# 4.net
KiCad netlist of a schematic drawn in Altium Designer
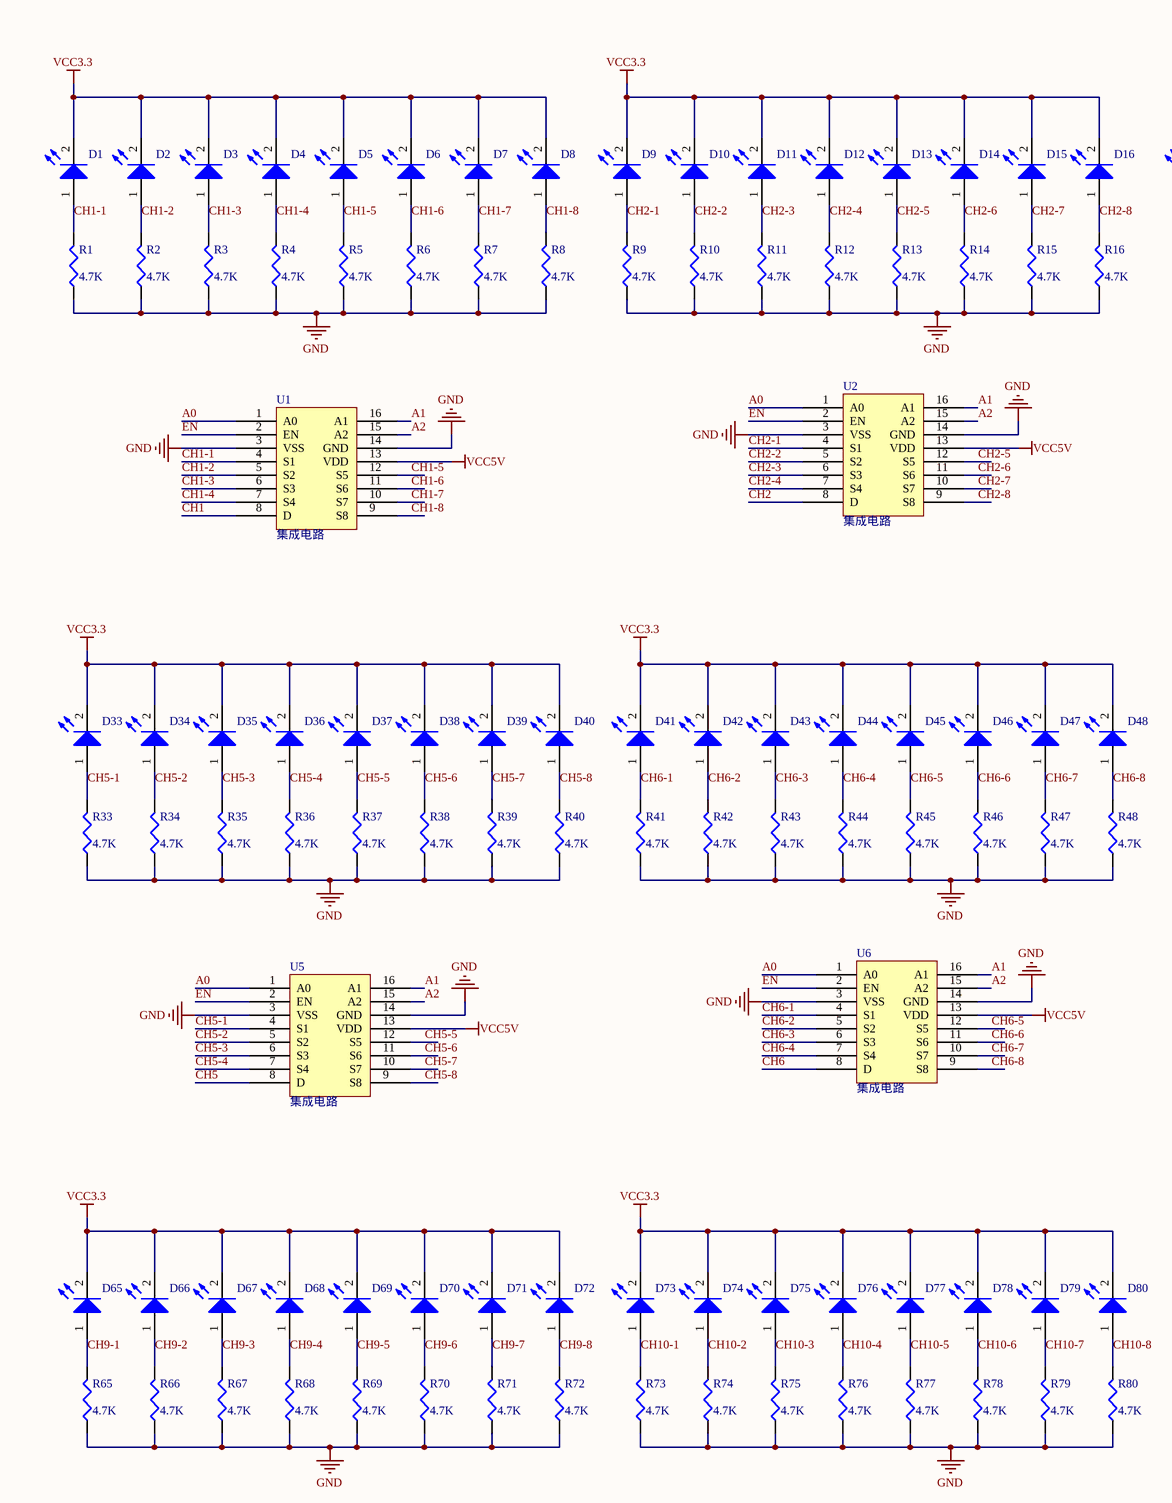
[diagram p0: 数粒机接收板4通道.SchDoc, top left]
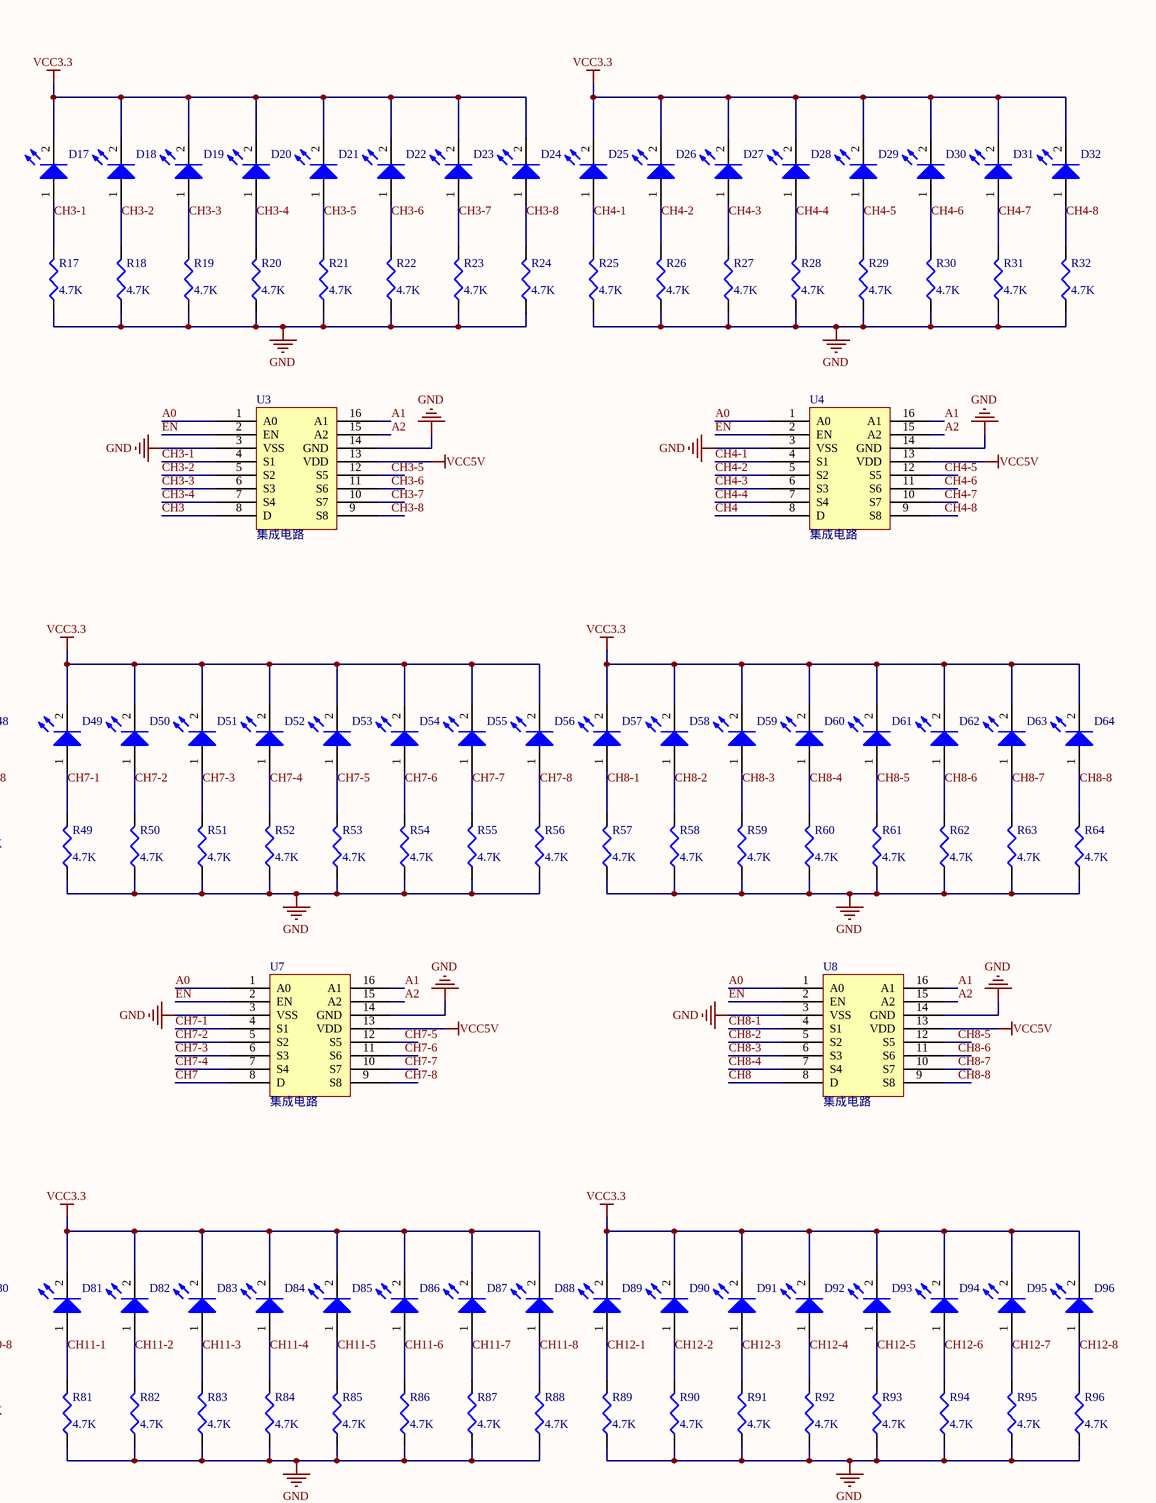
[diagram p1: 数粒机接收板4通道.SchDoc, top right]
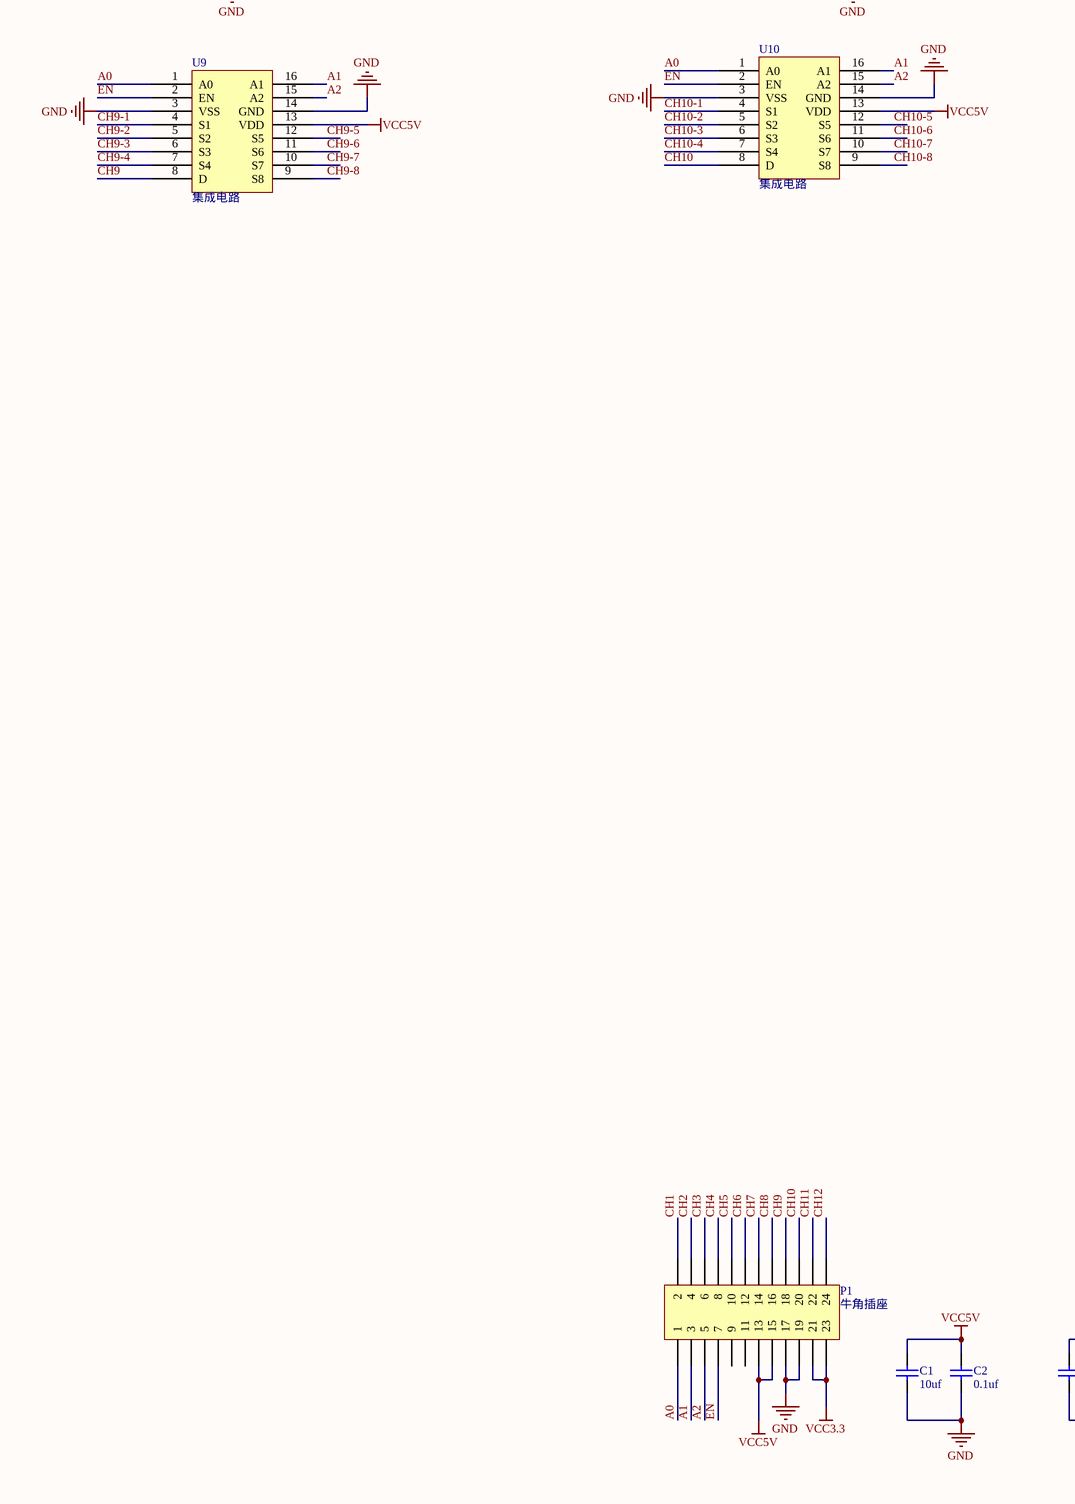
[diagram p2: 数粒机接收板4通道.SchDoc, bottom left]
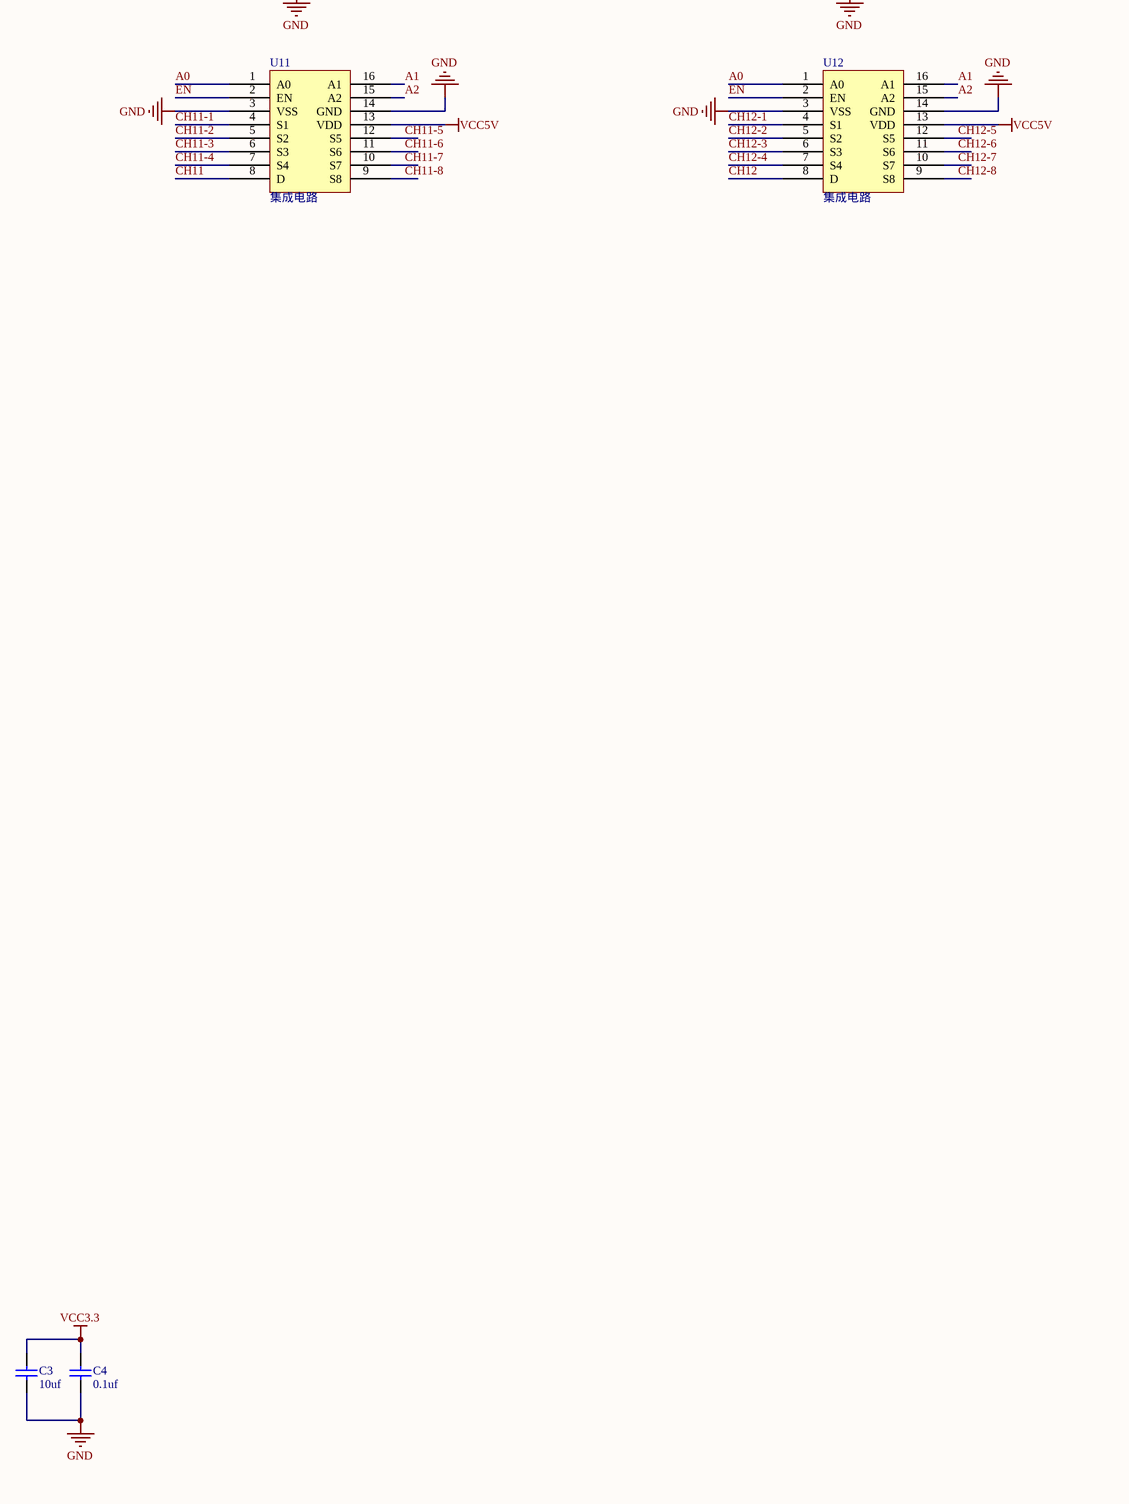
[diagram p3: 数粒机接收板4通道.SchDoc, bottom right]

(export (version "E")
  (design (tool "Eeschema 10.0.6"))
  (components
    (comp (ref "C1")
      (value "10uf")
      (footprint "0805c")
      (description "Capacitor")
      (fields (field (name "Comment") "贴片电容 10uf") (field (name "PUBLISHER") "Altium Limited"))
      (libsource (lib "Miscellaneous Devices") (part "Cap"))
    )
    (comp (ref "C2")
      (value "0.1uf")
      (footprint "0805c")
      (description "Capacitor 0.1uf")
      (fields (field (name "Comment") "贴片电容") (field (name "PUBLISHER") "Altium Limited"))
      (libsource (lib "Miscellaneous Devices") (part "Cap"))
    )
    (comp (ref "C3")
      (value "10uf")
      (footprint "0805c")
      (description "Capacitor")
      (fields (field (name "Comment") "贴片电容 10uf") (field (name "PUBLISHER") "Altium Limited"))
      (libsource (lib "Miscellaneous Devices") (part "Cap"))
    )
    (comp (ref "C4")
      (value "0.1uf")
      (footprint "0805c")
      (description "Capacitor 0.1uf")
      (fields (field (name "Comment") "贴片电容") (field (name "PUBLISHER") "Altium Limited"))
      (libsource (lib "Miscellaneous Devices") (part "Cap"))
    )
    (comp (ref "D1")
      (value "红外接收珠子")
      (footprint "jieshou1206")
      (description "PD15-21B/TR8")
      (fields (field (name "PUBLISHER") "Altium Limited"))
      (libsource (lib "Miscellaneous Devices") (part "PD15-21B/TR8"))
    )
    (comp (ref "D2")
      (value "红外接收珠子")
      (footprint "jieshou1206")
      (description "PD15-21B/TR8")
      (fields (field (name "PUBLISHER") "Altium Limited"))
      (libsource (lib "Miscellaneous Devices") (part "PD15-21B/TR8"))
    )
    (comp (ref "D3")
      (value "红外接收珠子")
      (footprint "jieshou1206")
      (description "PD15-21B/TR8")
      (fields (field (name "PUBLISHER") "Altium Limited"))
      (libsource (lib "Miscellaneous Devices") (part "PD15-21B/TR8"))
    )
    (comp (ref "D4")
      (value "红外接收珠子")
      (footprint "jieshou1206")
      (description "PD15-21B/TR8")
      (fields (field (name "PUBLISHER") "Altium Limited"))
      (libsource (lib "Miscellaneous Devices") (part "PD15-21B/TR8"))
    )
    (comp (ref "D5")
      (value "红外接收珠子")
      (footprint "jieshou1206")
      (description "PD15-21B/TR8")
      (fields (field (name "PUBLISHER") "Altium Limited"))
      (libsource (lib "Miscellaneous Devices") (part "PD15-21B/TR8"))
    )
    (comp (ref "D6")
      (value "红外接收珠子")
      (footprint "jieshou1206")
      (description "PD15-21B/TR8")
      (fields (field (name "PUBLISHER") "Altium Limited"))
      (libsource (lib "Miscellaneous Devices") (part "PD15-21B/TR8"))
    )
    (comp (ref "D7")
      (value "红外接收珠子")
      (footprint "jieshou1206")
      (description "PD15-21B/TR8")
      (fields (field (name "PUBLISHER") "Altium Limited"))
      (libsource (lib "Miscellaneous Devices") (part "PD15-21B/TR8"))
    )
    (comp (ref "D8")
      (value "红外接收珠子")
      (footprint "jieshou1206")
      (description "PD15-21B/TR8")
      (fields (field (name "PUBLISHER") "Altium Limited"))
      (libsource (lib "Miscellaneous Devices") (part "PD15-21B/TR8"))
    )
    (comp (ref "D9")
      (value "红外接收珠子")
      (footprint "jieshou1206")
      (description "PD15-21B/TR8")
      (fields (field (name "PUBLISHER") "Altium Limited"))
      (libsource (lib "Miscellaneous Devices") (part "PD15-21B/TR8"))
    )
    (comp (ref "D10")
      (value "红外接收珠子")
      (footprint "jieshou1206")
      (description "PD15-21B/TR8")
      (fields (field (name "PUBLISHER") "Altium Limited"))
      (libsource (lib "Miscellaneous Devices") (part "PD15-21B/TR8"))
    )
    (comp (ref "D11")
      (value "红外接收珠子")
      (footprint "jieshou1206")
      (description "PD15-21B/TR8")
      (fields (field (name "PUBLISHER") "Altium Limited"))
      (libsource (lib "Miscellaneous Devices") (part "PD15-21B/TR8"))
    )
    (comp (ref "D12")
      (value "红外接收珠子")
      (footprint "jieshou1206")
      (description "PD15-21B/TR8")
      (fields (field (name "PUBLISHER") "Altium Limited"))
      (libsource (lib "Miscellaneous Devices") (part "PD15-21B/TR8"))
    )
    (comp (ref "D13")
      (value "红外接收珠子")
      (footprint "jieshou1206")
      (description "PD15-21B/TR8")
      (fields (field (name "PUBLISHER") "Altium Limited"))
      (libsource (lib "Miscellaneous Devices") (part "PD15-21B/TR8"))
    )
    (comp (ref "D14")
      (value "红外接收珠子")
      (footprint "jieshou1206")
      (description "PD15-21B/TR8")
      (fields (field (name "PUBLISHER") "Altium Limited"))
      (libsource (lib "Miscellaneous Devices") (part "PD15-21B/TR8"))
    )
    (comp (ref "D15")
      (value "红外接收珠子")
      (footprint "jieshou1206")
      (description "PD15-21B/TR8")
      (fields (field (name "PUBLISHER") "Altium Limited"))
      (libsource (lib "Miscellaneous Devices") (part "PD15-21B/TR8"))
    )
    (comp (ref "D16")
      (value "红外接收珠子")
      (footprint "jieshou1206")
      (description "PD15-21B/TR8")
      (fields (field (name "PUBLISHER") "Altium Limited"))
      (libsource (lib "Miscellaneous Devices") (part "PD15-21B/TR8"))
    )
    (comp (ref "D17")
      (value "红外接收珠子")
      (footprint "jieshou1206")
      (description "PD15-21B/TR8")
      (fields (field (name "PUBLISHER") "Altium Limited"))
      (libsource (lib "Miscellaneous Devices") (part "PD15-21B/TR8"))
    )
    (comp (ref "D18")
      (value "红外接收珠子")
      (footprint "jieshou1206")
      (description "PD15-21B/TR8")
      (fields (field (name "PUBLISHER") "Altium Limited"))
      (libsource (lib "Miscellaneous Devices") (part "PD15-21B/TR8"))
    )
    (comp (ref "D19")
      (value "红外接收珠子")
      (footprint "jieshou1206")
      (description "PD15-21B/TR8")
      (fields (field (name "PUBLISHER") "Altium Limited"))
      (libsource (lib "Miscellaneous Devices") (part "PD15-21B/TR8"))
    )
    (comp (ref "D20")
      (value "红外接收珠子")
      (footprint "jieshou1206")
      (description "PD15-21B/TR8")
      (fields (field (name "PUBLISHER") "Altium Limited"))
      (libsource (lib "Miscellaneous Devices") (part "PD15-21B/TR8"))
    )
    (comp (ref "D21")
      (value "红外接收珠子")
      (footprint "jieshou1206")
      (description "PD15-21B/TR8")
      (fields (field (name "PUBLISHER") "Altium Limited"))
      (libsource (lib "Miscellaneous Devices") (part "PD15-21B/TR8"))
    )
    (comp (ref "D22")
      (value "红外接收珠子")
      (footprint "jieshou1206")
      (description "PD15-21B/TR8")
      (fields (field (name "PUBLISHER") "Altium Limited"))
      (libsource (lib "Miscellaneous Devices") (part "PD15-21B/TR8"))
    )
    (comp (ref "D23")
      (value "红外接收珠子")
      (footprint "jieshou1206")
      (description "PD15-21B/TR8")
      (fields (field (name "PUBLISHER") "Altium Limited"))
      (libsource (lib "Miscellaneous Devices") (part "PD15-21B/TR8"))
    )
    (comp (ref "D24")
      (value "红外接收珠子")
      (footprint "jieshou1206")
      (description "PD15-21B/TR8")
      (fields (field (name "PUBLISHER") "Altium Limited"))
      (libsource (lib "Miscellaneous Devices") (part "PD15-21B/TR8"))
    )
    (comp (ref "D25")
      (value "红外接收珠子")
      (footprint "jieshou1206")
      (description "PD15-21B/TR8")
      (fields (field (name "PUBLISHER") "Altium Limited"))
      (libsource (lib "Miscellaneous Devices") (part "PD15-21B/TR8"))
    )
    (comp (ref "D26")
      (value "红外接收珠子")
      (footprint "jieshou1206")
      (description "PD15-21B/TR8")
      (fields (field (name "PUBLISHER") "Altium Limited"))
      (libsource (lib "Miscellaneous Devices") (part "PD15-21B/TR8"))
    )
    (comp (ref "D27")
      (value "红外接收珠子")
      (footprint "jieshou1206")
      (description "PD15-21B/TR8")
      (fields (field (name "PUBLISHER") "Altium Limited"))
      (libsource (lib "Miscellaneous Devices") (part "PD15-21B/TR8"))
    )
    (comp (ref "D28")
      (value "红外接收珠子")
      (footprint "jieshou1206")
      (description "PD15-21B/TR8")
      (fields (field (name "PUBLISHER") "Altium Limited"))
      (libsource (lib "Miscellaneous Devices") (part "PD15-21B/TR8"))
    )
    (comp (ref "D29")
      (value "红外接收珠子")
      (footprint "jieshou1206")
      (description "PD15-21B/TR8")
      (fields (field (name "PUBLISHER") "Altium Limited"))
      (libsource (lib "Miscellaneous Devices") (part "PD15-21B/TR8"))
    )
    (comp (ref "D30")
      (value "红外接收珠子")
      (footprint "jieshou1206")
      (description "PD15-21B/TR8")
      (fields (field (name "PUBLISHER") "Altium Limited"))
      (libsource (lib "Miscellaneous Devices") (part "PD15-21B/TR8"))
    )
    (comp (ref "D31")
      (value "红外接收珠子")
      (footprint "jieshou1206")
      (description "PD15-21B/TR8")
      (fields (field (name "PUBLISHER") "Altium Limited"))
      (libsource (lib "Miscellaneous Devices") (part "PD15-21B/TR8"))
    )
    (comp (ref "D32")
      (value "红外接收珠子")
      (footprint "jieshou1206")
      (description "PD15-21B/TR8")
      (fields (field (name "PUBLISHER") "Altium Limited"))
      (libsource (lib "Miscellaneous Devices") (part "PD15-21B/TR8"))
    )
    (comp (ref "D33")
      (value "红外接收珠子")
      (footprint "jieshou1206")
      (description "PD15-21B/TR8")
      (fields (field (name "PUBLISHER") "Altium Limited"))
      (libsource (lib "Miscellaneous Devices") (part "PD15-21B/TR8"))
    )
    (comp (ref "D34")
      (value "红外接收珠子")
      (footprint "jieshou1206")
      (description "PD15-21B/TR8")
      (fields (field (name "PUBLISHER") "Altium Limited"))
      (libsource (lib "Miscellaneous Devices") (part "PD15-21B/TR8"))
    )
    (comp (ref "D35")
      (value "红外接收珠子")
      (footprint "jieshou1206")
      (description "PD15-21B/TR8")
      (fields (field (name "PUBLISHER") "Altium Limited"))
      (libsource (lib "Miscellaneous Devices") (part "PD15-21B/TR8"))
    )
    (comp (ref "D36")
      (value "红外接收珠子")
      (footprint "jieshou1206")
      (description "PD15-21B/TR8")
      (fields (field (name "PUBLISHER") "Altium Limited"))
      (libsource (lib "Miscellaneous Devices") (part "PD15-21B/TR8"))
    )
    (comp (ref "D37")
      (value "红外接收珠子")
      (footprint "jieshou1206")
      (description "PD15-21B/TR8")
      (fields (field (name "PUBLISHER") "Altium Limited"))
      (libsource (lib "Miscellaneous Devices") (part "PD15-21B/TR8"))
    )
    (comp (ref "D38")
      (value "红外接收珠子")
      (footprint "jieshou1206")
      (description "PD15-21B/TR8")
      (fields (field (name "PUBLISHER") "Altium Limited"))
      (libsource (lib "Miscellaneous Devices") (part "PD15-21B/TR8"))
    )
    (comp (ref "D39")
      (value "红外接收珠子")
      (footprint "jieshou1206")
      (description "PD15-21B/TR8")
      (fields (field (name "PUBLISHER") "Altium Limited"))
      (libsource (lib "Miscellaneous Devices") (part "PD15-21B/TR8"))
    )
    (comp (ref "D40")
      (value "红外接收珠子")
      (footprint "jieshou1206")
      (description "PD15-21B/TR8")
      (fields (field (name "PUBLISHER") "Altium Limited"))
      (libsource (lib "Miscellaneous Devices") (part "PD15-21B/TR8"))
    )
    (comp (ref "D41")
      (value "红外接收珠子")
      (footprint "jieshou1206")
      (description "PD15-21B/TR8")
      (fields (field (name "PUBLISHER") "Altium Limited"))
      (libsource (lib "Miscellaneous Devices") (part "PD15-21B/TR8"))
    )
    (comp (ref "D42")
      (value "红外接收珠子")
      (footprint "jieshou1206")
      (description "PD15-21B/TR8")
      (fields (field (name "PUBLISHER") "Altium Limited"))
      (libsource (lib "Miscellaneous Devices") (part "PD15-21B/TR8"))
    )
    (comp (ref "D43")
      (value "红外接收珠子")
      (footprint "jieshou1206")
      (description "PD15-21B/TR8")
      (fields (field (name "PUBLISHER") "Altium Limited"))
      (libsource (lib "Miscellaneous Devices") (part "PD15-21B/TR8"))
    )
    (comp (ref "D44")
      (value "红外接收珠子")
      (footprint "jieshou1206")
      (description "PD15-21B/TR8")
      (fields (field (name "PUBLISHER") "Altium Limited"))
      (libsource (lib "Miscellaneous Devices") (part "PD15-21B/TR8"))
    )
    (comp (ref "D45")
      (value "红外接收珠子")
      (footprint "jieshou1206")
      (description "PD15-21B/TR8")
      (fields (field (name "PUBLISHER") "Altium Limited"))
      (libsource (lib "Miscellaneous Devices") (part "PD15-21B/TR8"))
    )
    (comp (ref "D46")
      (value "红外接收珠子")
      (footprint "jieshou1206")
      (description "PD15-21B/TR8")
      (fields (field (name "PUBLISHER") "Altium Limited"))
      (libsource (lib "Miscellaneous Devices") (part "PD15-21B/TR8"))
    )
    (comp (ref "D47")
      (value "红外接收珠子")
      (footprint "jieshou1206")
      (description "PD15-21B/TR8")
      (fields (field (name "PUBLISHER") "Altium Limited"))
      (libsource (lib "Miscellaneous Devices") (part "PD15-21B/TR8"))
    )
    (comp (ref "D48")
      (value "红外接收珠子")
      (footprint "jieshou1206")
      (description "PD15-21B/TR8")
      (fields (field (name "PUBLISHER") "Altium Limited"))
      (libsource (lib "Miscellaneous Devices") (part "PD15-21B/TR8"))
    )
    (comp (ref "D49")
      (value "红外接收珠子")
      (footprint "jieshou1206")
      (description "PD15-21B/TR8")
      (fields (field (name "PUBLISHER") "Altium Limited"))
      (libsource (lib "Miscellaneous Devices") (part "PD15-21B/TR8"))
    )
    (comp (ref "D50")
      (value "红外接收珠子")
      (footprint "jieshou1206")
      (description "PD15-21B/TR8")
      (fields (field (name "PUBLISHER") "Altium Limited"))
      (libsource (lib "Miscellaneous Devices") (part "PD15-21B/TR8"))
    )
    (comp (ref "D51")
      (value "红外接收珠子")
      (footprint "jieshou1206")
      (description "PD15-21B/TR8")
      (fields (field (name "PUBLISHER") "Altium Limited"))
      (libsource (lib "Miscellaneous Devices") (part "PD15-21B/TR8"))
    )
    (comp (ref "D52")
      (value "红外接收珠子")
      (footprint "jieshou1206")
      (description "PD15-21B/TR8")
      (fields (field (name "PUBLISHER") "Altium Limited"))
      (libsource (lib "Miscellaneous Devices") (part "PD15-21B/TR8"))
    )
    (comp (ref "D53")
      (value "红外接收珠子")
      (footprint "jieshou1206")
      (description "PD15-21B/TR8")
      (fields (field (name "PUBLISHER") "Altium Limited"))
      (libsource (lib "Miscellaneous Devices") (part "PD15-21B/TR8"))
    )
    (comp (ref "D54")
      (value "红外接收珠子")
      (footprint "jieshou1206")
      (description "PD15-21B/TR8")
      (fields (field (name "PUBLISHER") "Altium Limited"))
      (libsource (lib "Miscellaneous Devices") (part "PD15-21B/TR8"))
    )
    (comp (ref "D55")
      (value "红外接收珠子")
      (footprint "jieshou1206")
      (description "PD15-21B/TR8")
      (fields (field (name "PUBLISHER") "Altium Limited"))
      (libsource (lib "Miscellaneous Devices") (part "PD15-21B/TR8"))
    )
    (comp (ref "D56")
      (value "红外接收珠子")
      (footprint "jieshou1206")
      (description "PD15-21B/TR8")
      (fields (field (name "PUBLISHER") "Altium Limited"))
      (libsource (lib "Miscellaneous Devices") (part "PD15-21B/TR8"))
    )
    (comp (ref "D57")
      (value "红外接收珠子")
      (footprint "jieshou1206")
      (description "PD15-21B/TR8")
      (fields (field (name "PUBLISHER") "Altium Limited"))
      (libsource (lib "Miscellaneous Devices") (part "PD15-21B/TR8"))
    )
    (comp (ref "D58")
      (value "红外接收珠子")
      (footprint "jieshou1206")
      (description "PD15-21B/TR8")
      (fields (field (name "PUBLISHER") "Altium Limited"))
      (libsource (lib "Miscellaneous Devices") (part "PD15-21B/TR8"))
    )
    (comp (ref "D59")
      (value "红外接收珠子")
      (footprint "jieshou1206")
      (description "PD15-21B/TR8")
      (fields (field (name "PUBLISHER") "Altium Limited"))
      (libsource (lib "Miscellaneous Devices") (part "PD15-21B/TR8"))
    )
    (comp (ref "D60")
      (value "红外接收珠子")
      (footprint "jieshou1206")
      (description "PD15-21B/TR8")
      (fields (field (name "PUBLISHER") "Altium Limited"))
      (libsource (lib "Miscellaneous Devices") (part "PD15-21B/TR8"))
    )
    (comp (ref "D61")
      (value "红外接收珠子")
      (footprint "jieshou1206")
      (description "PD15-21B/TR8")
      (fields (field (name "PUBLISHER") "Altium Limited"))
      (libsource (lib "Miscellaneous Devices") (part "PD15-21B/TR8"))
    )
    (comp (ref "D62")
      (value "红外接收珠子")
      (footprint "jieshou1206")
      (description "PD15-21B/TR8")
      (fields (field (name "PUBLISHER") "Altium Limited"))
      (libsource (lib "Miscellaneous Devices") (part "PD15-21B/TR8"))
    )
    (comp (ref "D63")
      (value "红外接收珠子")
      (footprint "jieshou1206")
      (description "PD15-21B/TR8")
      (fields (field (name "PUBLISHER") "Altium Limited"))
      (libsource (lib "Miscellaneous Devices") (part "PD15-21B/TR8"))
    )
    (comp (ref "D64")
      (value "红外接收珠子")
      (footprint "jieshou1206")
      (description "PD15-21B/TR8")
      (fields (field (name "PUBLISHER") "Altium Limited"))
      (libsource (lib "Miscellaneous Devices") (part "PD15-21B/TR8"))
    )
    (comp (ref "D65")
      (value "红外接收珠子")
      (footprint "jieshou1206")
      (description "PD15-21B/TR8")
      (fields (field (name "PUBLISHER") "Altium Limited"))
      (libsource (lib "Miscellaneous Devices") (part "PD15-21B/TR8"))
    )
    (comp (ref "D66")
      (value "红外接收珠子")
      (footprint "jieshou1206")
      (description "PD15-21B/TR8")
      (fields (field (name "PUBLISHER") "Altium Limited"))
      (libsource (lib "Miscellaneous Devices") (part "PD15-21B/TR8"))
    )
    (comp (ref "D67")
      (value "红外接收珠子")
      (footprint "jieshou1206")
      (description "PD15-21B/TR8")
      (fields (field (name "PUBLISHER") "Altium Limited"))
      (libsource (lib "Miscellaneous Devices") (part "PD15-21B/TR8"))
    )
    (comp (ref "D68")
      (value "红外接收珠子")
      (footprint "jieshou1206")
      (description "PD15-21B/TR8")
      (fields (field (name "PUBLISHER") "Altium Limited"))
      (libsource (lib "Miscellaneous Devices") (part "PD15-21B/TR8"))
    )
    (comp (ref "D69")
      (value "红外接收珠子")
      (footprint "jieshou1206")
      (description "PD15-21B/TR8")
      (fields (field (name "PUBLISHER") "Altium Limited"))
      (libsource (lib "Miscellaneous Devices") (part "PD15-21B/TR8"))
    )
    (comp (ref "D70")
      (value "红外接收珠子")
      (footprint "jieshou1206")
      (description "PD15-21B/TR8")
      (fields (field (name "PUBLISHER") "Altium Limited"))
      (libsource (lib "Miscellaneous Devices") (part "PD15-21B/TR8"))
    )
    (comp (ref "D71")
      (value "红外接收珠子")
      (footprint "jieshou1206")
      (description "PD15-21B/TR8")
      (fields (field (name "PUBLISHER") "Altium Limited"))
      (libsource (lib "Miscellaneous Devices") (part "PD15-21B/TR8"))
    )
    (comp (ref "D72")
      (value "红外接收珠子")
      (footprint "jieshou1206")
      (description "PD15-21B/TR8")
      (fields (field (name "PUBLISHER") "Altium Limited"))
      (libsource (lib "Miscellaneous Devices") (part "PD15-21B/TR8"))
    )
    (comp (ref "D73")
      (value "红外接收珠子")
      (footprint "jieshou1206")
      (description "PD15-21B/TR8")
      (fields (field (name "PUBLISHER") "Altium Limited"))
      (libsource (lib "Miscellaneous Devices") (part "PD15-21B/TR8"))
    )
    (comp (ref "D74")
      (value "红外接收珠子")
      (footprint "jieshou1206")
      (description "PD15-21B/TR8")
      (fields (field (name "PUBLISHER") "Altium Limited"))
      (libsource (lib "Miscellaneous Devices") (part "PD15-21B/TR8"))
    )
    (comp (ref "D75")
      (value "红外接收珠子")
      (footprint "jieshou1206")
      (description "PD15-21B/TR8")
      (fields (field (name "PUBLISHER") "Altium Limited"))
      (libsource (lib "Miscellaneous Devices") (part "PD15-21B/TR8"))
    )
    (comp (ref "D76")
      (value "红外接收珠子")
      (footprint "jieshou1206")
      (description "PD15-21B/TR8")
      (fields (field (name "PUBLISHER") "Altium Limited"))
      (libsource (lib "Miscellaneous Devices") (part "PD15-21B/TR8"))
    )
    (comp (ref "D77")
      (value "红外接收珠子")
      (footprint "jieshou1206")
      (description "PD15-21B/TR8")
      (fields (field (name "PUBLISHER") "Altium Limited"))
      (libsource (lib "Miscellaneous Devices") (part "PD15-21B/TR8"))
    )
    (comp (ref "D78")
      (value "红外接收珠子")
      (footprint "jieshou1206")
      (description "PD15-21B/TR8")
      (fields (field (name "PUBLISHER") "Altium Limited"))
      (libsource (lib "Miscellaneous Devices") (part "PD15-21B/TR8"))
    )
    (comp (ref "D79")
      (value "红外接收珠子")
      (footprint "jieshou1206")
      (description "PD15-21B/TR8")
      (fields (field (name "PUBLISHER") "Altium Limited"))
      (libsource (lib "Miscellaneous Devices") (part "PD15-21B/TR8"))
    )
    (comp (ref "D80")
      (value "红外接收珠子")
      (footprint "jieshou1206")
      (description "PD15-21B/TR8")
      (fields (field (name "PUBLISHER") "Altium Limited"))
      (libsource (lib "Miscellaneous Devices") (part "PD15-21B/TR8"))
    )
    (comp (ref "D81")
      (value "红外接收珠子")
      (footprint "jieshou1206")
      (description "PD15-21B/TR8")
      (fields (field (name "PUBLISHER") "Altium Limited"))
      (libsource (lib "Miscellaneous Devices") (part "PD15-21B/TR8"))
    )
    (comp (ref "D82")
      (value "红外接收珠子")
      (footprint "jieshou1206")
      (description "PD15-21B/TR8")
      (fields (field (name "PUBLISHER") "Altium Limited"))
      (libsource (lib "Miscellaneous Devices") (part "PD15-21B/TR8"))
    )
    (comp (ref "D83")
      (value "红外接收珠子")
      (footprint "jieshou1206")
      (description "PD15-21B/TR8")
      (fields (field (name "PUBLISHER") "Altium Limited"))
      (libsource (lib "Miscellaneous Devices") (part "PD15-21B/TR8"))
    )
    (comp (ref "D84")
      (value "红外接收珠子")
      (footprint "jieshou1206")
      (description "PD15-21B/TR8")
      (fields (field (name "PUBLISHER") "Altium Limited"))
      (libsource (lib "Miscellaneous Devices") (part "PD15-21B/TR8"))
    )
    (comp (ref "D85")
      (value "红外接收珠子")
      (footprint "jieshou1206")
      (description "PD15-21B/TR8")
      (fields (field (name "PUBLISHER") "Altium Limited"))
      (libsource (lib "Miscellaneous Devices") (part "PD15-21B/TR8"))
    )
    (comp (ref "D86")
      (value "红外接收珠子")
      (footprint "jieshou1206")
      (description "PD15-21B/TR8")
      (fields (field (name "PUBLISHER") "Altium Limited"))
      (libsource (lib "Miscellaneous Devices") (part "PD15-21B/TR8"))
    )
    (comp (ref "D87")
      (value "红外接收珠子")
      (footprint "jieshou1206")
      (description "PD15-21B/TR8")
      (fields (field (name "PUBLISHER") "Altium Limited"))
      (libsource (lib "Miscellaneous Devices") (part "PD15-21B/TR8"))
    )
    (comp (ref "D88")
      (value "红外接收珠子")
      (footprint "jieshou1206")
      (description "PD15-21B/TR8")
      (fields (field (name "PUBLISHER") "Altium Limited"))
      (libsource (lib "Miscellaneous Devices") (part "PD15-21B/TR8"))
    )
    (comp (ref "D89")
      (value "红外接收珠子")
      (footprint "jieshou1206")
      (description "PD15-21B/TR8")
      (fields (field (name "PUBLISHER") "Altium Limited"))
      (libsource (lib "Miscellaneous Devices") (part "PD15-21B/TR8"))
    )
    (comp (ref "D90")
      (value "红外接收珠子")
      (footprint "jieshou1206")
      (description "PD15-21B/TR8")
      (fields (field (name "PUBLISHER") "Altium Limited"))
      (libsource (lib "Miscellaneous Devices") (part "PD15-21B/TR8"))
    )
    (comp (ref "D91")
      (value "红外接收珠子")
      (footprint "jieshou1206")
      (description "PD15-21B/TR8")
      (fields (field (name "PUBLISHER") "Altium Limited"))
      (libsource (lib "Miscellaneous Devices") (part "PD15-21B/TR8"))
    )
    (comp (ref "D92")
      (value "红外接收珠子")
      (footprint "jieshou1206")
      (description "PD15-21B/TR8")
      (fields (field (name "PUBLISHER") "Altium Limited"))
      (libsource (lib "Miscellaneous Devices") (part "PD15-21B/TR8"))
    )
    (comp (ref "D93")
      (value "红外接收珠子")
      (footprint "jieshou1206")
      (description "PD15-21B/TR8")
      (fields (field (name "PUBLISHER") "Altium Limited"))
      (libsource (lib "Miscellaneous Devices") (part "PD15-21B/TR8"))
    )
    (comp (ref "D94")
      (value "红外接收珠子")
      (footprint "jieshou1206")
      (description "PD15-21B/TR8")
      (fields (field (name "PUBLISHER") "Altium Limited"))
      (libsource (lib "Miscellaneous Devices") (part "PD15-21B/TR8"))
    )
    (comp (ref "D95")
      (value "红外接收珠子")
      (footprint "jieshou1206")
      (description "PD15-21B/TR8")
      (fields (field (name "PUBLISHER") "Altium Limited"))
      (libsource (lib "Miscellaneous Devices") (part "PD15-21B/TR8"))
    )
    (comp (ref "D96")
      (value "红外接收珠子")
      (footprint "jieshou1206")
      (description "PD15-21B/TR8")
      (fields (field (name "PUBLISHER") "Altium Limited"))
      (libsource (lib "Miscellaneous Devices") (part "PD15-21B/TR8"))
    )
    (comp (ref "P1")
      (value "牛角插座")
      (footprint "HDR2X12")
      (description "Header, 12-Pin, Dual row")
      (fields (field (name "PUBLISHER") "Altium Limited"))
      (libsource (lib "Miscellaneous Connectors") (part "Header 12X2"))
    )
    (comp (ref "R1")
      (value "4.7K")
      (footprint "0805r")
      (description "电阻")
      (fields (field (name "Comment") "贴片电阻") (field (name "PUBLISHER") "Altium Limited"))
      (libsource (lib "Miscellaneous Devices") (part "Res3"))
    )
    (comp (ref "R2")
      (value "4.7K")
      (footprint "0805r")
      (description "电阻")
      (fields (field (name "Comment") "贴片电阻") (field (name "PUBLISHER") "Altium Limited"))
      (libsource (lib "Miscellaneous Devices") (part "Res3"))
    )
    (comp (ref "R3")
      (value "4.7K")
      (footprint "0805r")
      (description "电阻")
      (fields (field (name "Comment") "贴片电阻") (field (name "PUBLISHER") "Altium Limited"))
      (libsource (lib "Miscellaneous Devices") (part "Res3"))
    )
    (comp (ref "R4")
      (value "4.7K")
      (footprint "0805r")
      (description "电阻")
      (fields (field (name "Comment") "贴片电阻") (field (name "PUBLISHER") "Altium Limited"))
      (libsource (lib "Miscellaneous Devices") (part "Res3"))
    )
    (comp (ref "R5")
      (value "4.7K")
      (footprint "0805r")
      (description "电阻")
      (fields (field (name "Comment") "贴片电阻") (field (name "PUBLISHER") "Altium Limited"))
      (libsource (lib "Miscellaneous Devices") (part "Res3"))
    )
    (comp (ref "R6")
      (value "4.7K")
      (footprint "0805r")
      (description "电阻")
      (fields (field (name "Comment") "贴片电阻") (field (name "PUBLISHER") "Altium Limited"))
      (libsource (lib "Miscellaneous Devices") (part "Res3"))
    )
    (comp (ref "R7")
      (value "4.7K")
      (footprint "0805r")
      (description "电阻")
      (fields (field (name "Comment") "贴片电阻") (field (name "PUBLISHER") "Altium Limited"))
      (libsource (lib "Miscellaneous Devices") (part "Res3"))
    )
    (comp (ref "R8")
      (value "4.7K")
      (footprint "0805r")
      (description "电阻")
      (fields (field (name "Comment") "贴片电阻") (field (name "PUBLISHER") "Altium Limited"))
      (libsource (lib "Miscellaneous Devices") (part "Res3"))
    )
    (comp (ref "R9")
      (value "4.7K")
      (footprint "0805r")
      (description "电阻")
      (fields (field (name "Comment") "贴片电阻") (field (name "PUBLISHER") "Altium Limited"))
      (libsource (lib "Miscellaneous Devices") (part "Res3"))
    )
    (comp (ref "R10")
      (value "4.7K")
      (footprint "0805r")
      (description "电阻")
      (fields (field (name "Comment") "贴片电阻") (field (name "PUBLISHER") "Altium Limited"))
      (libsource (lib "Miscellaneous Devices") (part "Res3"))
    )
    (comp (ref "R11")
      (value "4.7K")
      (footprint "0805r")
      (description "电阻")
      (fields (field (name "Comment") "贴片电阻") (field (name "PUBLISHER") "Altium Limited"))
      (libsource (lib "Miscellaneous Devices") (part "Res3"))
    )
    (comp (ref "R12")
      (value "4.7K")
      (footprint "0805r")
      (description "电阻")
      (fields (field (name "Comment") "贴片电阻") (field (name "PUBLISHER") "Altium Limited"))
      (libsource (lib "Miscellaneous Devices") (part "Res3"))
    )
    (comp (ref "R13")
      (value "4.7K")
      (footprint "0805r")
      (description "电阻")
      (fields (field (name "Comment") "贴片电阻") (field (name "PUBLISHER") "Altium Limited"))
      (libsource (lib "Miscellaneous Devices") (part "Res3"))
    )
    (comp (ref "R14")
      (value "4.7K")
      (footprint "0805r")
      (description "电阻")
      (fields (field (name "Comment") "贴片电阻") (field (name "PUBLISHER") "Altium Limited"))
      (libsource (lib "Miscellaneous Devices") (part "Res3"))
    )
    (comp (ref "R15")
      (value "4.7K")
      (footprint "0805r")
      (description "电阻")
      (fields (field (name "Comment") "贴片电阻") (field (name "PUBLISHER") "Altium Limited"))
      (libsource (lib "Miscellaneous Devices") (part "Res3"))
    )
    (comp (ref "R16")
      (value "4.7K")
      (footprint "0805r")
      (description "电阻")
      (fields (field (name "Comment") "贴片电阻") (field (name "PUBLISHER") "Altium Limited"))
      (libsource (lib "Miscellaneous Devices") (part "Res3"))
    )
    (comp (ref "R17")
      (value "4.7K")
      (footprint "0805r")
      (description "电阻")
      (fields (field (name "Comment") "贴片电阻") (field (name "PUBLISHER") "Altium Limited"))
      (libsource (lib "Miscellaneous Devices") (part "Res3"))
    )
    (comp (ref "R18")
      (value "4.7K")
      (footprint "0805r")
      (description "电阻")
      (fields (field (name "Comment") "贴片电阻") (field (name "PUBLISHER") "Altium Limited"))
      (libsource (lib "Miscellaneous Devices") (part "Res3"))
    )
    (comp (ref "R19")
      (value "4.7K")
      (footprint "0805r")
      (description "电阻")
      (fields (field (name "Comment") "贴片电阻") (field (name "PUBLISHER") "Altium Limited"))
      (libsource (lib "Miscellaneous Devices") (part "Res3"))
    )
    (comp (ref "R20")
      (value "4.7K")
      (footprint "0805r")
      (description "电阻")
      (fields (field (name "Comment") "贴片电阻") (field (name "PUBLISHER") "Altium Limited"))
      (libsource (lib "Miscellaneous Devices") (part "Res3"))
    )
    (comp (ref "R21")
      (value "4.7K")
      (footprint "0805r")
      (description "电阻")
      (fields (field (name "Comment") "贴片电阻") (field (name "PUBLISHER") "Altium Limited"))
      (libsource (lib "Miscellaneous Devices") (part "Res3"))
    )
    (comp (ref "R22")
      (value "4.7K")
      (footprint "0805r")
      (description "电阻")
      (fields (field (name "Comment") "贴片电阻") (field (name "PUBLISHER") "Altium Limited"))
      (libsource (lib "Miscellaneous Devices") (part "Res3"))
    )
    (comp (ref "R23")
      (value "4.7K")
      (footprint "0805r")
      (description "电阻")
      (fields (field (name "Comment") "贴片电阻") (field (name "PUBLISHER") "Altium Limited"))
      (libsource (lib "Miscellaneous Devices") (part "Res3"))
    )
    (comp (ref "R24")
      (value "4.7K")
      (footprint "0805r")
      (description "电阻")
      (fields (field (name "Comment") "贴片电阻") (field (name "PUBLISHER") "Altium Limited"))
      (libsource (lib "Miscellaneous Devices") (part "Res3"))
    )
    (comp (ref "R25")
      (value "4.7K")
      (footprint "0805r")
      (description "电阻")
      (fields (field (name "Comment") "贴片电阻") (field (name "PUBLISHER") "Altium Limited"))
      (libsource (lib "Miscellaneous Devices") (part "Res3"))
    )
    (comp (ref "R26")
      (value "4.7K")
      (footprint "0805r")
      (description "电阻")
      (fields (field (name "Comment") "贴片电阻") (field (name "PUBLISHER") "Altium Limited"))
      (libsource (lib "Miscellaneous Devices") (part "Res3"))
    )
    (comp (ref "R27")
      (value "4.7K")
      (footprint "0805r")
      (description "电阻")
      (fields (field (name "Comment") "贴片电阻") (field (name "PUBLISHER") "Altium Limited"))
      (libsource (lib "Miscellaneous Devices") (part "Res3"))
    )
    (comp (ref "R28")
      (value "4.7K")
      (footprint "0805r")
      (description "电阻")
      (fields (field (name "Comment") "贴片电阻") (field (name "PUBLISHER") "Altium Limited"))
      (libsource (lib "Miscellaneous Devices") (part "Res3"))
    )
    (comp (ref "R29")
      (value "4.7K")
      (footprint "0805r")
      (description "电阻")
      (fields (field (name "Comment") "贴片电阻") (field (name "PUBLISHER") "Altium Limited"))
      (libsource (lib "Miscellaneous Devices") (part "Res3"))
    )
    (comp (ref "R30")
      (value "4.7K")
      (footprint "0805r")
      (description "电阻")
      (fields (field (name "Comment") "贴片电阻") (field (name "PUBLISHER") "Altium Limited"))
      (libsource (lib "Miscellaneous Devices") (part "Res3"))
    )
    (comp (ref "R31")
      (value "4.7K")
      (footprint "0805r")
      (description "电阻")
      (fields (field (name "Comment") "贴片电阻") (field (name "PUBLISHER") "Altium Limited"))
      (libsource (lib "Miscellaneous Devices") (part "Res3"))
    )
    (comp (ref "R32")
      (value "4.7K")
      (footprint "0805r")
      (description "电阻")
      (fields (field (name "Comment") "贴片电阻") (field (name "PUBLISHER") "Altium Limited"))
      (libsource (lib "Miscellaneous Devices") (part "Res3"))
    )
    (comp (ref "R33")
      (value "4.7K")
      (footprint "0805r")
      (description "电阻")
      (fields (field (name "Comment") "贴片电阻") (field (name "PUBLISHER") "Altium Limited"))
      (libsource (lib "Miscellaneous Devices") (part "Res3"))
    )
    (comp (ref "R34")
      (value "4.7K")
      (footprint "0805r")
      (description "电阻")
      (fields (field (name "Comment") "贴片电阻") (field (name "PUBLISHER") "Altium Limited"))
      (libsource (lib "Miscellaneous Devices") (part "Res3"))
    )
    (comp (ref "R35")
      (value "4.7K")
      (footprint "0805r")
      (description "电阻")
      (fields (field (name "Comment") "贴片电阻") (field (name "PUBLISHER") "Altium Limited"))
      (libsource (lib "Miscellaneous Devices") (part "Res3"))
    )
    (comp (ref "R36")
      (value "4.7K")
      (footprint "0805r")
      (description "电阻")
      (fields (field (name "Comment") "贴片电阻") (field (name "PUBLISHER") "Altium Limited"))
      (libsource (lib "Miscellaneous Devices") (part "Res3"))
    )
    (comp (ref "R37")
      (value "4.7K")
      (footprint "0805r")
      (description "电阻")
      (fields (field (name "Comment") "贴片电阻") (field (name "PUBLISHER") "Altium Limited"))
      (libsource (lib "Miscellaneous Devices") (part "Res3"))
    )
    (comp (ref "R38")
      (value "4.7K")
      (footprint "0805r")
      (description "电阻")
      (fields (field (name "Comment") "贴片电阻") (field (name "PUBLISHER") "Altium Limited"))
      (libsource (lib "Miscellaneous Devices") (part "Res3"))
    )
    (comp (ref "R39")
      (value "4.7K")
      (footprint "0805r")
      (description "电阻")
      (fields (field (name "Comment") "贴片电阻") (field (name "PUBLISHER") "Altium Limited"))
      (libsource (lib "Miscellaneous Devices") (part "Res3"))
    )
    (comp (ref "R40")
      (value "4.7K")
      (footprint "0805r")
      (description "电阻")
      (fields (field (name "Comment") "贴片电阻") (field (name "PUBLISHER") "Altium Limited"))
      (libsource (lib "Miscellaneous Devices") (part "Res3"))
    )
    (comp (ref "R41")
      (value "4.7K")
      (footprint "0805r")
      (description "电阻")
      (fields (field (name "Comment") "贴片电阻") (field (name "PUBLISHER") "Altium Limited"))
      (libsource (lib "Miscellaneous Devices") (part "Res3"))
    )
    (comp (ref "R42")
      (value "4.7K")
      (footprint "0805r")
      (description "电阻")
      (fields (field (name "Comment") "贴片电阻") (field (name "PUBLISHER") "Altium Limited"))
      (libsource (lib "Miscellaneous Devices") (part "Res3"))
    )
    (comp (ref "R43")
      (value "4.7K")
      (footprint "0805r")
      (description "电阻")
      (fields (field (name "Comment") "贴片电阻") (field (name "PUBLISHER") "Altium Limited"))
      (libsource (lib "Miscellaneous Devices") (part "Res3"))
    )
    (comp (ref "R44")
      (value "4.7K")
      (footprint "0805r")
      (description "电阻")
      (fields (field (name "Comment") "贴片电阻") (field (name "PUBLISHER") "Altium Limited"))
      (libsource (lib "Miscellaneous Devices") (part "Res3"))
    )
    (comp (ref "R45")
      (value "4.7K")
      (footprint "0805r")
      (description "电阻")
      (fields (field (name "Comment") "贴片电阻") (field (name "PUBLISHER") "Altium Limited"))
      (libsource (lib "Miscellaneous Devices") (part "Res3"))
    )
    (comp (ref "R46")
      (value "4.7K")
      (footprint "0805r")
      (description "电阻")
      (fields (field (name "Comment") "贴片电阻") (field (name "PUBLISHER") "Altium Limited"))
      (libsource (lib "Miscellaneous Devices") (part "Res3"))
    )
    (comp (ref "R47")
      (value "4.7K")
      (footprint "0805r")
      (description "电阻")
      (fields (field (name "Comment") "贴片电阻") (field (name "PUBLISHER") "Altium Limited"))
      (libsource (lib "Miscellaneous Devices") (part "Res3"))
    )
    (comp (ref "R48")
      (value "4.7K")
      (footprint "0805r")
      (description "电阻")
      (fields (field (name "Comment") "贴片电阻") (field (name "PUBLISHER") "Altium Limited"))
      (libsource (lib "Miscellaneous Devices") (part "Res3"))
    )
    (comp (ref "R49")
      (value "4.7K")
      (footprint "0805r")
      (description "电阻")
      (fields (field (name "Comment") "贴片电阻") (field (name "PUBLISHER") "Altium Limited"))
      (libsource (lib "Miscellaneous Devices") (part "Res3"))
    )
    (comp (ref "R50")
      (value "4.7K")
      (footprint "0805r")
      (description "电阻")
      (fields (field (name "Comment") "贴片电阻") (field (name "PUBLISHER") "Altium Limited"))
      (libsource (lib "Miscellaneous Devices") (part "Res3"))
    )
    (comp (ref "R51")
      (value "4.7K")
      (footprint "0805r")
      (description "电阻")
      (fields (field (name "Comment") "贴片电阻") (field (name "PUBLISHER") "Altium Limited"))
      (libsource (lib "Miscellaneous Devices") (part "Res3"))
    )
    (comp (ref "R52")
      (value "4.7K")
      (footprint "0805r")
      (description "电阻")
      (fields (field (name "Comment") "贴片电阻") (field (name "PUBLISHER") "Altium Limited"))
      (libsource (lib "Miscellaneous Devices") (part "Res3"))
    )
    (comp (ref "R53")
      (value "4.7K")
      (footprint "0805r")
      (description "电阻")
      (fields (field (name "Comment") "贴片电阻") (field (name "PUBLISHER") "Altium Limited"))
      (libsource (lib "Miscellaneous Devices") (part "Res3"))
    )
    (comp (ref "R54")
      (value "4.7K")
      (footprint "0805r")
      (description "电阻")
      (fields (field (name "Comment") "贴片电阻") (field (name "PUBLISHER") "Altium Limited"))
      (libsource (lib "Miscellaneous Devices") (part "Res3"))
    )
    (comp (ref "R55")
      (value "4.7K")
      (footprint "0805r")
      (description "电阻")
      (fields (field (name "Comment") "贴片电阻") (field (name "PUBLISHER") "Altium Limited"))
      (libsource (lib "Miscellaneous Devices") (part "Res3"))
    )
    (comp (ref "R56")
      (value "4.7K")
      (footprint "0805r")
      (description "电阻")
      (fields (field (name "Comment") "贴片电阻") (field (name "PUBLISHER") "Altium Limited"))
      (libsource (lib "Miscellaneous Devices") (part "Res3"))
    )
    (comp (ref "R57")
      (value "4.7K")
      (footprint "0805r")
      (description "电阻")
      (fields (field (name "Comment") "贴片电阻") (field (name "PUBLISHER") "Altium Limited"))
      (libsource (lib "Miscellaneous Devices") (part "Res3"))
    )
    (comp (ref "R58")
      (value "4.7K")
      (footprint "0805r")
      (description "电阻")
      (fields (field (name "Comment") "贴片电阻") (field (name "PUBLISHER") "Altium Limited"))
      (libsource (lib "Miscellaneous Devices") (part "Res3"))
    )
    (comp (ref "R59")
      (value "4.7K")
      (footprint "0805r")
      (description "电阻")
      (fields (field (name "Comment") "贴片电阻") (field (name "PUBLISHER") "Altium Limited"))
      (libsource (lib "Miscellaneous Devices") (part "Res3"))
    )
    (comp (ref "R60")
      (value "4.7K")
      (footprint "0805r")
      (description "电阻")
      (fields (field (name "Comment") "贴片电阻") (field (name "PUBLISHER") "Altium Limited"))
      (libsource (lib "Miscellaneous Devices") (part "Res3"))
    )
    (comp (ref "R61")
      (value "4.7K")
      (footprint "0805r")
      (description "电阻")
      (fields (field (name "Comment") "贴片电阻") (field (name "PUBLISHER") "Altium Limited"))
      (libsource (lib "Miscellaneous Devices") (part "Res3"))
    )
    (comp (ref "R62")
      (value "4.7K")
      (footprint "0805r")
      (description "电阻")
      (fields (field (name "Comment") "贴片电阻") (field (name "PUBLISHER") "Altium Limited"))
      (libsource (lib "Miscellaneous Devices") (part "Res3"))
    )
    (comp (ref "R63")
      (value "4.7K")
      (footprint "0805r")
      (description "电阻")
      (fields (field (name "Comment") "贴片电阻") (field (name "PUBLISHER") "Altium Limited"))
      (libsource (lib "Miscellaneous Devices") (part "Res3"))
    )
    (comp (ref "R64")
      (value "4.7K")
      (footprint "0805r")
      (description "电阻")
      (fields (field (name "Comment") "贴片电阻") (field (name "PUBLISHER") "Altium Limited"))
      (libsource (lib "Miscellaneous Devices") (part "Res3"))
    )
    (comp (ref "R65")
      (value "4.7K")
      (footprint "0805r")
      (description "电阻")
      (fields (field (name "Comment") "贴片电阻") (field (name "PUBLISHER") "Altium Limited"))
      (libsource (lib "Miscellaneous Devices") (part "Res3"))
    )
    (comp (ref "R66")
      (value "4.7K")
      (footprint "0805r")
      (description "电阻")
      (fields (field (name "Comment") "贴片电阻") (field (name "PUBLISHER") "Altium Limited"))
      (libsource (lib "Miscellaneous Devices") (part "Res3"))
    )
    (comp (ref "R67")
      (value "4.7K")
      (footprint "0805r")
      (description "电阻")
      (fields (field (name "Comment") "贴片电阻") (field (name "PUBLISHER") "Altium Limited"))
      (libsource (lib "Miscellaneous Devices") (part "Res3"))
    )
    (comp (ref "R68")
      (value "4.7K")
      (footprint "0805r")
      (description "电阻")
      (fields (field (name "Comment") "贴片电阻") (field (name "PUBLISHER") "Altium Limited"))
      (libsource (lib "Miscellaneous Devices") (part "Res3"))
    )
    (comp (ref "R69")
      (value "4.7K")
      (footprint "0805r")
      (description "电阻")
      (fields (field (name "Comment") "贴片电阻") (field (name "PUBLISHER") "Altium Limited"))
      (libsource (lib "Miscellaneous Devices") (part "Res3"))
    )
    (comp (ref "R70")
      (value "4.7K")
      (footprint "0805r")
      (description "电阻")
      (fields (field (name "Comment") "贴片电阻") (field (name "PUBLISHER") "Altium Limited"))
      (libsource (lib "Miscellaneous Devices") (part "Res3"))
    )
    (comp (ref "R71")
      (value "4.7K")
      (footprint "0805r")
      (description "电阻")
      (fields (field (name "Comment") "贴片电阻") (field (name "PUBLISHER") "Altium Limited"))
      (libsource (lib "Miscellaneous Devices") (part "Res3"))
    )
    (comp (ref "R72")
      (value "4.7K")
      (footprint "0805r")
      (description "电阻")
      (fields (field (name "Comment") "贴片电阻") (field (name "PUBLISHER") "Altium Limited"))
      (libsource (lib "Miscellaneous Devices") (part "Res3"))
    )
    (comp (ref "R73")
      (value "4.7K")
      (footprint "0805r")
      (description "电阻")
      (fields (field (name "Comment") "贴片电阻") (field (name "PUBLISHER") "Altium Limited"))
      (libsource (lib "Miscellaneous Devices") (part "Res3"))
    )
    (comp (ref "R74")
      (value "4.7K")
      (footprint "0805r")
      (description "电阻")
      (fields (field (name "Comment") "贴片电阻") (field (name "PUBLISHER") "Altium Limited"))
      (libsource (lib "Miscellaneous Devices") (part "Res3"))
    )
    (comp (ref "R75")
      (value "4.7K")
      (footprint "0805r")
      (description "电阻")
      (fields (field (name "Comment") "贴片电阻") (field (name "PUBLISHER") "Altium Limited"))
      (libsource (lib "Miscellaneous Devices") (part "Res3"))
    )
    (comp (ref "R76")
      (value "4.7K")
      (footprint "0805r")
      (description "电阻")
      (fields (field (name "Comment") "贴片电阻") (field (name "PUBLISHER") "Altium Limited"))
      (libsource (lib "Miscellaneous Devices") (part "Res3"))
    )
    (comp (ref "R77")
      (value "4.7K")
      (footprint "0805r")
      (description "电阻")
      (fields (field (name "Comment") "贴片电阻") (field (name "PUBLISHER") "Altium Limited"))
      (libsource (lib "Miscellaneous Devices") (part "Res3"))
    )
    (comp (ref "R78")
      (value "4.7K")
      (footprint "0805r")
      (description "电阻")
      (fields (field (name "Comment") "贴片电阻") (field (name "PUBLISHER") "Altium Limited"))
      (libsource (lib "Miscellaneous Devices") (part "Res3"))
    )
    (comp (ref "R79")
      (value "4.7K")
      (footprint "0805r")
      (description "电阻")
      (fields (field (name "Comment") "贴片电阻") (field (name "PUBLISHER") "Altium Limited"))
      (libsource (lib "Miscellaneous Devices") (part "Res3"))
    )
    (comp (ref "R80")
      (value "4.7K")
      (footprint "0805r")
      (description "电阻")
      (fields (field (name "Comment") "贴片电阻") (field (name "PUBLISHER") "Altium Limited"))
      (libsource (lib "Miscellaneous Devices") (part "Res3"))
    )
    (comp (ref "R81")
      (value "4.7K")
      (footprint "0805r")
      (description "电阻")
      (fields (field (name "Comment") "贴片电阻") (field (name "PUBLISHER") "Altium Limited"))
      (libsource (lib "Miscellaneous Devices") (part "Res3"))
    )
    (comp (ref "R82")
      (value "4.7K")
      (footprint "0805r")
      (description "电阻")
      (fields (field (name "Comment") "贴片电阻") (field (name "PUBLISHER") "Altium Limited"))
      (libsource (lib "Miscellaneous Devices") (part "Res3"))
    )
    (comp (ref "R83")
      (value "4.7K")
      (footprint "0805r")
      (description "电阻")
      (fields (field (name "Comment") "贴片电阻") (field (name "PUBLISHER") "Altium Limited"))
      (libsource (lib "Miscellaneous Devices") (part "Res3"))
    )
    (comp (ref "R84")
      (value "4.7K")
      (footprint "0805r")
      (description "电阻")
      (fields (field (name "Comment") "贴片电阻") (field (name "PUBLISHER") "Altium Limited"))
      (libsource (lib "Miscellaneous Devices") (part "Res3"))
    )
    (comp (ref "R85")
      (value "4.7K")
      (footprint "0805r")
      (description "电阻")
      (fields (field (name "Comment") "贴片电阻") (field (name "PUBLISHER") "Altium Limited"))
      (libsource (lib "Miscellaneous Devices") (part "Res3"))
    )
    (comp (ref "R86")
      (value "4.7K")
      (footprint "0805r")
      (description "电阻")
      (fields (field (name "Comment") "贴片电阻") (field (name "PUBLISHER") "Altium Limited"))
      (libsource (lib "Miscellaneous Devices") (part "Res3"))
    )
    (comp (ref "R87")
      (value "4.7K")
      (footprint "0805r")
      (description "电阻")
      (fields (field (name "Comment") "贴片电阻") (field (name "PUBLISHER") "Altium Limited"))
      (libsource (lib "Miscellaneous Devices") (part "Res3"))
    )
    (comp (ref "R88")
      (value "4.7K")
      (footprint "0805r")
      (description "电阻")
      (fields (field (name "Comment") "贴片电阻") (field (name "PUBLISHER") "Altium Limited"))
      (libsource (lib "Miscellaneous Devices") (part "Res3"))
    )
    (comp (ref "R89")
      (value "4.7K")
      (footprint "0805r")
      (description "电阻")
      (fields (field (name "Comment") "贴片电阻") (field (name "PUBLISHER") "Altium Limited"))
      (libsource (lib "Miscellaneous Devices") (part "Res3"))
    )
    (comp (ref "R90")
      (value "4.7K")
      (footprint "0805r")
      (description "电阻")
      (fields (field (name "Comment") "贴片电阻") (field (name "PUBLISHER") "Altium Limited"))
      (libsource (lib "Miscellaneous Devices") (part "Res3"))
    )
    (comp (ref "R91")
      (value "4.7K")
      (footprint "0805r")
      (description "电阻")
      (fields (field (name "Comment") "贴片电阻") (field (name "PUBLISHER") "Altium Limited"))
      (libsource (lib "Miscellaneous Devices") (part "Res3"))
    )
    (comp (ref "R92")
      (value "4.7K")
      (footprint "0805r")
      (description "电阻")
      (fields (field (name "Comment") "贴片电阻") (field (name "PUBLISHER") "Altium Limited"))
      (libsource (lib "Miscellaneous Devices") (part "Res3"))
    )
    (comp (ref "R93")
      (value "4.7K")
      (footprint "0805r")
      (description "电阻")
      (fields (field (name "Comment") "贴片电阻") (field (name "PUBLISHER") "Altium Limited"))
      (libsource (lib "Miscellaneous Devices") (part "Res3"))
    )
    (comp (ref "R94")
      (value "4.7K")
      (footprint "0805r")
      (description "电阻")
      (fields (field (name "Comment") "贴片电阻") (field (name "PUBLISHER") "Altium Limited"))
      (libsource (lib "Miscellaneous Devices") (part "Res3"))
    )
    (comp (ref "R95")
      (value "4.7K")
      (footprint "0805r")
      (description "电阻")
      (fields (field (name "Comment") "贴片电阻") (field (name "PUBLISHER") "Altium Limited"))
      (libsource (lib "Miscellaneous Devices") (part "Res3"))
    )
    (comp (ref "R96")
      (value "4.7K")
      (footprint "0805r")
      (description "电阻")
      (fields (field (name "Comment") "贴片电阻") (field (name "PUBLISHER") "Altium Limited"))
      (libsource (lib "Miscellaneous Devices") (part "Res3"))
    )
    (comp (ref "U1")
      (value "集成电路")
      (footprint "TSSOP16")
      (description "ADG708BRU-REEL")
      (libsource (lib "MYlib") (part "ADG708"))
    )
    (comp (ref "U2")
      (value "集成电路")
      (footprint "TSSOP16")
      (description "ADG708BRU-REEL")
      (libsource (lib "MYlib") (part "ADG708"))
    )
    (comp (ref "U3")
      (value "集成电路")
      (footprint "TSSOP16")
      (description "ADG708BRU-REEL")
      (libsource (lib "MYlib") (part "ADG708"))
    )
    (comp (ref "U4")
      (value "集成电路")
      (footprint "TSSOP16")
      (description "ADG708BRU-REEL")
      (libsource (lib "MYlib") (part "ADG708"))
    )
    (comp (ref "U5")
      (value "集成电路")
      (footprint "TSSOP16")
      (description "ADG708BRU-REEL")
      (libsource (lib "MYlib") (part "ADG708"))
    )
    (comp (ref "U6")
      (value "集成电路")
      (footprint "TSSOP16")
      (description "ADG708BRU-REEL")
      (libsource (lib "MYlib") (part "ADG708"))
    )
    (comp (ref "U7")
      (value "集成电路")
      (footprint "TSSOP16")
      (description "ADG708BRU-REEL")
      (libsource (lib "MYlib") (part "ADG708"))
    )
    (comp (ref "U8")
      (value "集成电路")
      (footprint "TSSOP16")
      (description "ADG708BRU-REEL")
      (libsource (lib "MYlib") (part "ADG708"))
    )
    (comp (ref "U9")
      (value "集成电路")
      (footprint "TSSOP16")
      (description "ADG708BRU-REEL")
      (libsource (lib "MYlib") (part "ADG708"))
    )
    (comp (ref "U10")
      (value "集成电路")
      (footprint "TSSOP16")
      (description "ADG708BRU-REEL")
      (libsource (lib "MYlib") (part "ADG708"))
    )
    (comp (ref "U11")
      (value "集成电路")
      (footprint "TSSOP16")
      (description "ADG708BRU-REEL")
      (libsource (lib "MYlib") (part "ADG708"))
    )
    (comp (ref "U12")
      (value "集成电路")
      (footprint "TSSOP16")
      (description "ADG708BRU-REEL")
      (libsource (lib "MYlib") (part "ADG708"))
    )
  )
  (nets
    (net (code "1") (name "/A0") (class "Default")
      (node (ref "P1") (pin "1") (pinfunction "1_1") (pintype "passive"))
      (node (ref "U1") (pin "1") (pinfunction "A0_1") (pintype "passive"))
      (node (ref "U10") (pin "1") (pinfunction "A0_1") (pintype "passive"))
      (node (ref "U11") (pin "1") (pinfunction "A0_1") (pintype "passive"))
      (node (ref "U12") (pin "1") (pinfunction "A0_1") (pintype "passive"))
      (node (ref "U2") (pin "1") (pinfunction "A0_1") (pintype "passive"))
      (node (ref "U3") (pin "1") (pinfunction "A0_1") (pintype "passive"))
      (node (ref "U4") (pin "1") (pinfunction "A0_1") (pintype "passive"))
      (node (ref "U5") (pin "1") (pinfunction "A0_1") (pintype "passive"))
      (node (ref "U6") (pin "1") (pinfunction "A0_1") (pintype "passive"))
      (node (ref "U7") (pin "1") (pinfunction "A0_1") (pintype "passive"))
      (node (ref "U8") (pin "1") (pinfunction "A0_1") (pintype "passive"))
      (node (ref "U9") (pin "1") (pinfunction "A0_1") (pintype "passive"))
    )
    (net (code "2") (name "/A1") (class "Default")
      (node (ref "P1") (pin "3") (pinfunction "3_3") (pintype "passive"))
      (node (ref "U1") (pin "16") (pinfunction "A1_16") (pintype "passive"))
      (node (ref "U10") (pin "16") (pinfunction "A1_16") (pintype "passive"))
      (node (ref "U11") (pin "16") (pinfunction "A1_16") (pintype "passive"))
      (node (ref "U12") (pin "16") (pinfunction "A1_16") (pintype "passive"))
      (node (ref "U2") (pin "16") (pinfunction "A1_16") (pintype "passive"))
      (node (ref "U3") (pin "16") (pinfunction "A1_16") (pintype "passive"))
      (node (ref "U4") (pin "16") (pinfunction "A1_16") (pintype "passive"))
      (node (ref "U5") (pin "16") (pinfunction "A1_16") (pintype "passive"))
      (node (ref "U6") (pin "16") (pinfunction "A1_16") (pintype "passive"))
      (node (ref "U7") (pin "16") (pinfunction "A1_16") (pintype "passive"))
      (node (ref "U8") (pin "16") (pinfunction "A1_16") (pintype "passive"))
      (node (ref "U9") (pin "16") (pinfunction "A1_16") (pintype "passive"))
    )
    (net (code "3") (name "/A2") (class "Default")
      (node (ref "P1") (pin "5") (pinfunction "5_5") (pintype "passive"))
      (node (ref "U1") (pin "15") (pinfunction "A2_15") (pintype "passive"))
      (node (ref "U10") (pin "15") (pinfunction "A2_15") (pintype "passive"))
      (node (ref "U11") (pin "15") (pinfunction "A2_15") (pintype "passive"))
      (node (ref "U12") (pin "15") (pinfunction "A2_15") (pintype "passive"))
      (node (ref "U2") (pin "15") (pinfunction "A2_15") (pintype "passive"))
      (node (ref "U3") (pin "15") (pinfunction "A2_15") (pintype "passive"))
      (node (ref "U4") (pin "15") (pinfunction "A2_15") (pintype "passive"))
      (node (ref "U5") (pin "15") (pinfunction "A2_15") (pintype "passive"))
      (node (ref "U6") (pin "15") (pinfunction "A2_15") (pintype "passive"))
      (node (ref "U7") (pin "15") (pinfunction "A2_15") (pintype "passive"))
      (node (ref "U8") (pin "15") (pinfunction "A2_15") (pintype "passive"))
      (node (ref "U9") (pin "15") (pinfunction "A2_15") (pintype "passive"))
    )
    (net (code "4") (name "/CH1") (class "Default")
      (node (ref "P1") (pin "2") (pinfunction "2_2") (pintype "passive"))
      (node (ref "U1") (pin "8") (pinfunction "D_8") (pintype "passive"))
    )
    (net (code "5") (name "/CH1-1") (class "Default")
      (node (ref "D1") (pin "1") (pinfunction "A_1") (pintype "passive"))
      (node (ref "R1") (pin "2") (pinfunction "2_2") (pintype "passive"))
      (node (ref "U1") (pin "4") (pinfunction "S1_4") (pintype "passive"))
    )
    (net (code "6") (name "/CH1-2") (class "Default")
      (node (ref "D2") (pin "1") (pinfunction "A_1") (pintype "passive"))
      (node (ref "R2") (pin "2") (pinfunction "2_2") (pintype "passive"))
      (node (ref "U1") (pin "5") (pinfunction "S2_5") (pintype "passive"))
    )
    (net (code "7") (name "/CH1-3") (class "Default")
      (node (ref "D3") (pin "1") (pinfunction "A_1") (pintype "passive"))
      (node (ref "R3") (pin "2") (pinfunction "2_2") (pintype "passive"))
      (node (ref "U1") (pin "6") (pinfunction "S3_6") (pintype "passive"))
    )
    (net (code "8") (name "/CH1-4") (class "Default")
      (node (ref "D4") (pin "1") (pinfunction "A_1") (pintype "passive"))
      (node (ref "R4") (pin "2") (pinfunction "2_2") (pintype "passive"))
      (node (ref "U1") (pin "7") (pinfunction "S4_7") (pintype "passive"))
    )
    (net (code "9") (name "/CH1-5") (class "Default")
      (node (ref "D5") (pin "1") (pinfunction "A_1") (pintype "passive"))
      (node (ref "R5") (pin "2") (pinfunction "2_2") (pintype "passive"))
      (node (ref "U1") (pin "12") (pinfunction "S5_12") (pintype "passive"))
    )
    (net (code "10") (name "/CH1-6") (class "Default")
      (node (ref "D6") (pin "1") (pinfunction "A_1") (pintype "passive"))
      (node (ref "R6") (pin "2") (pinfunction "2_2") (pintype "passive"))
      (node (ref "U1") (pin "11") (pinfunction "S6_11") (pintype "passive"))
    )
    (net (code "11") (name "/CH1-7") (class "Default")
      (node (ref "D7") (pin "1") (pinfunction "A_1") (pintype "passive"))
      (node (ref "R7") (pin "2") (pinfunction "2_2") (pintype "passive"))
      (node (ref "U1") (pin "10") (pinfunction "S7_10") (pintype "passive"))
    )
    (net (code "12") (name "/CH1-8") (class "Default")
      (node (ref "D8") (pin "1") (pinfunction "A_1") (pintype "passive"))
      (node (ref "R8") (pin "2") (pinfunction "2_2") (pintype "passive"))
      (node (ref "U1") (pin "9") (pinfunction "S8_9") (pintype "passive"))
    )
    (net (code "13") (name "/CH2") (class "Default")
      (node (ref "P1") (pin "4") (pinfunction "4_4") (pintype "passive"))
      (node (ref "U2") (pin "8") (pinfunction "D_8") (pintype "passive"))
    )
    (net (code "14") (name "/CH2-1") (class "Default")
      (node (ref "D9") (pin "1") (pinfunction "A_1") (pintype "passive"))
      (node (ref "R9") (pin "2") (pinfunction "2_2") (pintype "passive"))
      (node (ref "U2") (pin "4") (pinfunction "S1_4") (pintype "passive"))
    )
    (net (code "15") (name "/CH2-2") (class "Default")
      (node (ref "D10") (pin "1") (pinfunction "A_1") (pintype "passive"))
      (node (ref "R10") (pin "2") (pinfunction "2_2") (pintype "passive"))
      (node (ref "U2") (pin "5") (pinfunction "S2_5") (pintype "passive"))
    )
    (net (code "16") (name "/CH2-3") (class "Default")
      (node (ref "D11") (pin "1") (pinfunction "A_1") (pintype "passive"))
      (node (ref "R11") (pin "2") (pinfunction "2_2") (pintype "passive"))
      (node (ref "U2") (pin "6") (pinfunction "S3_6") (pintype "passive"))
    )
    (net (code "17") (name "/CH2-4") (class "Default")
      (node (ref "D12") (pin "1") (pinfunction "A_1") (pintype "passive"))
      (node (ref "R12") (pin "2") (pinfunction "2_2") (pintype "passive"))
      (node (ref "U2") (pin "7") (pinfunction "S4_7") (pintype "passive"))
    )
    (net (code "18") (name "/CH2-5") (class "Default")
      (node (ref "D13") (pin "1") (pinfunction "A_1") (pintype "passive"))
      (node (ref "R13") (pin "2") (pinfunction "2_2") (pintype "passive"))
      (node (ref "U2") (pin "12") (pinfunction "S5_12") (pintype "passive"))
    )
    (net (code "19") (name "/CH2-6") (class "Default")
      (node (ref "D14") (pin "1") (pinfunction "A_1") (pintype "passive"))
      (node (ref "R14") (pin "2") (pinfunction "2_2") (pintype "passive"))
      (node (ref "U2") (pin "11") (pinfunction "S6_11") (pintype "passive"))
    )
    (net (code "20") (name "/CH2-7") (class "Default")
      (node (ref "D15") (pin "1") (pinfunction "A_1") (pintype "passive"))
      (node (ref "R15") (pin "2") (pinfunction "2_2") (pintype "passive"))
      (node (ref "U2") (pin "10") (pinfunction "S7_10") (pintype "passive"))
    )
    (net (code "21") (name "/CH2-8") (class "Default")
      (node (ref "D16") (pin "1") (pinfunction "A_1") (pintype "passive"))
      (node (ref "R16") (pin "2") (pinfunction "2_2") (pintype "passive"))
      (node (ref "U2") (pin "9") (pinfunction "S8_9") (pintype "passive"))
    )
    (net (code "22") (name "/CH3") (class "Default")
      (node (ref "P1") (pin "6") (pinfunction "6_6") (pintype "passive"))
      (node (ref "U3") (pin "8") (pinfunction "D_8") (pintype "passive"))
    )
    (net (code "23") (name "/CH3-1") (class "Default")
      (node (ref "D17") (pin "1") (pinfunction "A_1") (pintype "passive"))
      (node (ref "R17") (pin "2") (pinfunction "2_2") (pintype "passive"))
      (node (ref "U3") (pin "4") (pinfunction "S1_4") (pintype "passive"))
    )
    (net (code "24") (name "/CH3-2") (class "Default")
      (node (ref "D18") (pin "1") (pinfunction "A_1") (pintype "passive"))
      (node (ref "R18") (pin "2") (pinfunction "2_2") (pintype "passive"))
      (node (ref "U3") (pin "5") (pinfunction "S2_5") (pintype "passive"))
    )
    (net (code "25") (name "/CH3-3") (class "Default")
      (node (ref "D19") (pin "1") (pinfunction "A_1") (pintype "passive"))
      (node (ref "R19") (pin "2") (pinfunction "2_2") (pintype "passive"))
      (node (ref "U3") (pin "6") (pinfunction "S3_6") (pintype "passive"))
    )
    (net (code "26") (name "/CH3-4") (class "Default")
      (node (ref "D20") (pin "1") (pinfunction "A_1") (pintype "passive"))
      (node (ref "R20") (pin "2") (pinfunction "2_2") (pintype "passive"))
      (node (ref "U3") (pin "7") (pinfunction "S4_7") (pintype "passive"))
    )
    (net (code "27") (name "/CH3-5") (class "Default")
      (node (ref "D21") (pin "1") (pinfunction "A_1") (pintype "passive"))
      (node (ref "R21") (pin "2") (pinfunction "2_2") (pintype "passive"))
      (node (ref "U3") (pin "12") (pinfunction "S5_12") (pintype "passive"))
    )
    (net (code "28") (name "/CH3-6") (class "Default")
      (node (ref "D22") (pin "1") (pinfunction "A_1") (pintype "passive"))
      (node (ref "R22") (pin "2") (pinfunction "2_2") (pintype "passive"))
      (node (ref "U3") (pin "11") (pinfunction "S6_11") (pintype "passive"))
    )
    (net (code "29") (name "/CH3-7") (class "Default")
      (node (ref "D23") (pin "1") (pinfunction "A_1") (pintype "passive"))
      (node (ref "R23") (pin "2") (pinfunction "2_2") (pintype "passive"))
      (node (ref "U3") (pin "10") (pinfunction "S7_10") (pintype "passive"))
    )
    (net (code "30") (name "/CH3-8") (class "Default")
      (node (ref "D24") (pin "1") (pinfunction "A_1") (pintype "passive"))
      (node (ref "R24") (pin "2") (pinfunction "2_2") (pintype "passive"))
      (node (ref "U3") (pin "9") (pinfunction "S8_9") (pintype "passive"))
    )
    (net (code "31") (name "/CH4") (class "Default")
      (node (ref "P1") (pin "8") (pinfunction "8_8") (pintype "passive"))
      (node (ref "U4") (pin "8") (pinfunction "D_8") (pintype "passive"))
    )
    (net (code "32") (name "/CH4-1") (class "Default")
      (node (ref "D25") (pin "1") (pinfunction "A_1") (pintype "passive"))
      (node (ref "R25") (pin "2") (pinfunction "2_2") (pintype "passive"))
      (node (ref "U4") (pin "4") (pinfunction "S1_4") (pintype "passive"))
    )
    (net (code "33") (name "/CH4-2") (class "Default")
      (node (ref "D26") (pin "1") (pinfunction "A_1") (pintype "passive"))
      (node (ref "R26") (pin "2") (pinfunction "2_2") (pintype "passive"))
      (node (ref "U4") (pin "5") (pinfunction "S2_5") (pintype "passive"))
    )
    (net (code "34") (name "/CH4-3") (class "Default")
      (node (ref "D27") (pin "1") (pinfunction "A_1") (pintype "passive"))
      (node (ref "R27") (pin "2") (pinfunction "2_2") (pintype "passive"))
      (node (ref "U4") (pin "6") (pinfunction "S3_6") (pintype "passive"))
    )
    (net (code "35") (name "/CH4-4") (class "Default")
      (node (ref "D28") (pin "1") (pinfunction "A_1") (pintype "passive"))
      (node (ref "R28") (pin "2") (pinfunction "2_2") (pintype "passive"))
      (node (ref "U4") (pin "7") (pinfunction "S4_7") (pintype "passive"))
    )
    (net (code "36") (name "/CH4-5") (class "Default")
      (node (ref "D29") (pin "1") (pinfunction "A_1") (pintype "passive"))
      (node (ref "R29") (pin "2") (pinfunction "2_2") (pintype "passive"))
      (node (ref "U4") (pin "12") (pinfunction "S5_12") (pintype "passive"))
    )
    (net (code "37") (name "/CH4-6") (class "Default")
      (node (ref "D30") (pin "1") (pinfunction "A_1") (pintype "passive"))
      (node (ref "R30") (pin "2") (pinfunction "2_2") (pintype "passive"))
      (node (ref "U4") (pin "11") (pinfunction "S6_11") (pintype "passive"))
    )
    (net (code "38") (name "/CH4-7") (class "Default")
      (node (ref "D31") (pin "1") (pinfunction "A_1") (pintype "passive"))
      (node (ref "R31") (pin "2") (pinfunction "2_2") (pintype "passive"))
      (node (ref "U4") (pin "10") (pinfunction "S7_10") (pintype "passive"))
    )
    (net (code "39") (name "/CH4-8") (class "Default")
      (node (ref "D32") (pin "1") (pinfunction "A_1") (pintype "passive"))
      (node (ref "R32") (pin "2") (pinfunction "2_2") (pintype "passive"))
      (node (ref "U4") (pin "9") (pinfunction "S8_9") (pintype "passive"))
    )
    (net (code "40") (name "/CH5") (class "Default")
      (node (ref "P1") (pin "10") (pinfunction "10_10") (pintype "passive"))
      (node (ref "U5") (pin "8") (pinfunction "D_8") (pintype "passive"))
    )
    (net (code "41") (name "/CH5-1") (class "Default")
      (node (ref "D33") (pin "1") (pinfunction "A_1") (pintype "passive"))
      (node (ref "R33") (pin "2") (pinfunction "2_2") (pintype "passive"))
      (node (ref "U5") (pin "4") (pinfunction "S1_4") (pintype "passive"))
    )
    (net (code "42") (name "/CH5-2") (class "Default")
      (node (ref "D34") (pin "1") (pinfunction "A_1") (pintype "passive"))
      (node (ref "R34") (pin "2") (pinfunction "2_2") (pintype "passive"))
      (node (ref "U5") (pin "5") (pinfunction "S2_5") (pintype "passive"))
    )
    (net (code "43") (name "/CH5-3") (class "Default")
      (node (ref "D35") (pin "1") (pinfunction "A_1") (pintype "passive"))
      (node (ref "R35") (pin "2") (pinfunction "2_2") (pintype "passive"))
      (node (ref "U5") (pin "6") (pinfunction "S3_6") (pintype "passive"))
    )
    (net (code "44") (name "/CH5-4") (class "Default")
      (node (ref "D36") (pin "1") (pinfunction "A_1") (pintype "passive"))
      (node (ref "R36") (pin "2") (pinfunction "2_2") (pintype "passive"))
      (node (ref "U5") (pin "7") (pinfunction "S4_7") (pintype "passive"))
    )
    (net (code "45") (name "/CH5-5") (class "Default")
      (node (ref "D37") (pin "1") (pinfunction "A_1") (pintype "passive"))
      (node (ref "R37") (pin "2") (pinfunction "2_2") (pintype "passive"))
      (node (ref "U5") (pin "12") (pinfunction "S5_12") (pintype "passive"))
    )
    (net (code "46") (name "/CH5-6") (class "Default")
      (node (ref "D38") (pin "1") (pinfunction "A_1") (pintype "passive"))
      (node (ref "R38") (pin "2") (pinfunction "2_2") (pintype "passive"))
      (node (ref "U5") (pin "11") (pinfunction "S6_11") (pintype "passive"))
    )
    (net (code "47") (name "/CH5-7") (class "Default")
      (node (ref "D39") (pin "1") (pinfunction "A_1") (pintype "passive"))
      (node (ref "R39") (pin "2") (pinfunction "2_2") (pintype "passive"))
      (node (ref "U5") (pin "10") (pinfunction "S7_10") (pintype "passive"))
    )
    (net (code "48") (name "/CH5-8") (class "Default")
      (node (ref "D40") (pin "1") (pinfunction "A_1") (pintype "passive"))
      (node (ref "R40") (pin "2") (pinfunction "2_2") (pintype "passive"))
      (node (ref "U5") (pin "9") (pinfunction "S8_9") (pintype "passive"))
    )
    (net (code "49") (name "/CH6") (class "Default")
      (node (ref "P1") (pin "12") (pinfunction "12_12") (pintype "passive"))
      (node (ref "U6") (pin "8") (pinfunction "D_8") (pintype "passive"))
    )
    (net (code "50") (name "/CH6-1") (class "Default")
      (node (ref "D41") (pin "1") (pinfunction "A_1") (pintype "passive"))
      (node (ref "R41") (pin "2") (pinfunction "2_2") (pintype "passive"))
      (node (ref "U6") (pin "4") (pinfunction "S1_4") (pintype "passive"))
    )
    (net (code "51") (name "/CH6-2") (class "Default")
      (node (ref "D42") (pin "1") (pinfunction "A_1") (pintype "passive"))
      (node (ref "R42") (pin "2") (pinfunction "2_2") (pintype "passive"))
      (node (ref "U6") (pin "5") (pinfunction "S2_5") (pintype "passive"))
    )
    (net (code "52") (name "/CH6-3") (class "Default")
      (node (ref "D43") (pin "1") (pinfunction "A_1") (pintype "passive"))
      (node (ref "R43") (pin "2") (pinfunction "2_2") (pintype "passive"))
      (node (ref "U6") (pin "6") (pinfunction "S3_6") (pintype "passive"))
    )
    (net (code "53") (name "/CH6-4") (class "Default")
      (node (ref "D44") (pin "1") (pinfunction "A_1") (pintype "passive"))
      (node (ref "R44") (pin "2") (pinfunction "2_2") (pintype "passive"))
      (node (ref "U6") (pin "7") (pinfunction "S4_7") (pintype "passive"))
    )
    (net (code "54") (name "/CH6-5") (class "Default")
      (node (ref "D45") (pin "1") (pinfunction "A_1") (pintype "passive"))
      (node (ref "R45") (pin "2") (pinfunction "2_2") (pintype "passive"))
      (node (ref "U6") (pin "12") (pinfunction "S5_12") (pintype "passive"))
    )
    (net (code "55") (name "/CH6-6") (class "Default")
      (node (ref "D46") (pin "1") (pinfunction "A_1") (pintype "passive"))
      (node (ref "R46") (pin "2") (pinfunction "2_2") (pintype "passive"))
      (node (ref "U6") (pin "11") (pinfunction "S6_11") (pintype "passive"))
    )
    (net (code "56") (name "/CH6-7") (class "Default")
      (node (ref "D47") (pin "1") (pinfunction "A_1") (pintype "passive"))
      (node (ref "R47") (pin "2") (pinfunction "2_2") (pintype "passive"))
      (node (ref "U6") (pin "10") (pinfunction "S7_10") (pintype "passive"))
    )
    (net (code "57") (name "/CH6-8") (class "Default")
      (node (ref "D48") (pin "1") (pinfunction "A_1") (pintype "passive"))
      (node (ref "R48") (pin "2") (pinfunction "2_2") (pintype "passive"))
      (node (ref "U6") (pin "9") (pinfunction "S8_9") (pintype "passive"))
    )
    (net (code "58") (name "/CH7") (class "Default")
      (node (ref "P1") (pin "14") (pinfunction "14_14") (pintype "passive"))
      (node (ref "U7") (pin "8") (pinfunction "D_8") (pintype "passive"))
    )
    (net (code "59") (name "/CH7-1") (class "Default")
      (node (ref "D49") (pin "1") (pinfunction "A_1") (pintype "passive"))
      (node (ref "R49") (pin "2") (pinfunction "2_2") (pintype "passive"))
      (node (ref "U7") (pin "4") (pinfunction "S1_4") (pintype "passive"))
    )
    (net (code "60") (name "/CH7-2") (class "Default")
      (node (ref "D50") (pin "1") (pinfunction "A_1") (pintype "passive"))
      (node (ref "R50") (pin "2") (pinfunction "2_2") (pintype "passive"))
      (node (ref "U7") (pin "5") (pinfunction "S2_5") (pintype "passive"))
    )
    (net (code "61") (name "/CH7-3") (class "Default")
      (node (ref "D51") (pin "1") (pinfunction "A_1") (pintype "passive"))
      (node (ref "R51") (pin "2") (pinfunction "2_2") (pintype "passive"))
      (node (ref "U7") (pin "6") (pinfunction "S3_6") (pintype "passive"))
    )
    (net (code "62") (name "/CH7-4") (class "Default")
      (node (ref "D52") (pin "1") (pinfunction "A_1") (pintype "passive"))
      (node (ref "R52") (pin "2") (pinfunction "2_2") (pintype "passive"))
      (node (ref "U7") (pin "7") (pinfunction "S4_7") (pintype "passive"))
    )
    (net (code "63") (name "/CH7-5") (class "Default")
      (node (ref "D53") (pin "1") (pinfunction "A_1") (pintype "passive"))
      (node (ref "R53") (pin "2") (pinfunction "2_2") (pintype "passive"))
      (node (ref "U7") (pin "12") (pinfunction "S5_12") (pintype "passive"))
    )
    (net (code "64") (name "/CH7-6") (class "Default")
      (node (ref "D54") (pin "1") (pinfunction "A_1") (pintype "passive"))
      (node (ref "R54") (pin "2") (pinfunction "2_2") (pintype "passive"))
      (node (ref "U7") (pin "11") (pinfunction "S6_11") (pintype "passive"))
    )
    (net (code "65") (name "/CH7-7") (class "Default")
      (node (ref "D55") (pin "1") (pinfunction "A_1") (pintype "passive"))
      (node (ref "R55") (pin "2") (pinfunction "2_2") (pintype "passive"))
      (node (ref "U7") (pin "10") (pinfunction "S7_10") (pintype "passive"))
    )
    (net (code "66") (name "/CH7-8") (class "Default")
      (node (ref "D56") (pin "1") (pinfunction "A_1") (pintype "passive"))
      (node (ref "R56") (pin "2") (pinfunction "2_2") (pintype "passive"))
      (node (ref "U7") (pin "9") (pinfunction "S8_9") (pintype "passive"))
    )
    (net (code "67") (name "/CH8") (class "Default")
      (node (ref "P1") (pin "16") (pinfunction "16_16") (pintype "passive"))
      (node (ref "U8") (pin "8") (pinfunction "D_8") (pintype "passive"))
    )
    (net (code "68") (name "/CH8-1") (class "Default")
      (node (ref "D57") (pin "1") (pinfunction "A_1") (pintype "passive"))
      (node (ref "R57") (pin "2") (pinfunction "2_2") (pintype "passive"))
      (node (ref "U8") (pin "4") (pinfunction "S1_4") (pintype "passive"))
    )
    (net (code "69") (name "/CH8-2") (class "Default")
      (node (ref "D58") (pin "1") (pinfunction "A_1") (pintype "passive"))
      (node (ref "R58") (pin "2") (pinfunction "2_2") (pintype "passive"))
      (node (ref "U8") (pin "5") (pinfunction "S2_5") (pintype "passive"))
    )
    (net (code "70") (name "/CH8-3") (class "Default")
      (node (ref "D59") (pin "1") (pinfunction "A_1") (pintype "passive"))
      (node (ref "R59") (pin "2") (pinfunction "2_2") (pintype "passive"))
      (node (ref "U8") (pin "6") (pinfunction "S3_6") (pintype "passive"))
    )
    (net (code "71") (name "/CH8-4") (class "Default")
      (node (ref "D60") (pin "1") (pinfunction "A_1") (pintype "passive"))
      (node (ref "R60") (pin "2") (pinfunction "2_2") (pintype "passive"))
      (node (ref "U8") (pin "7") (pinfunction "S4_7") (pintype "passive"))
    )
    (net (code "72") (name "/CH8-5") (class "Default")
      (node (ref "D61") (pin "1") (pinfunction "A_1") (pintype "passive"))
      (node (ref "R61") (pin "2") (pinfunction "2_2") (pintype "passive"))
      (node (ref "U8") (pin "12") (pinfunction "S5_12") (pintype "passive"))
    )
    (net (code "73") (name "/CH8-6") (class "Default")
      (node (ref "D62") (pin "1") (pinfunction "A_1") (pintype "passive"))
      (node (ref "R62") (pin "2") (pinfunction "2_2") (pintype "passive"))
      (node (ref "U8") (pin "11") (pinfunction "S6_11") (pintype "passive"))
    )
    (net (code "74") (name "/CH8-7") (class "Default")
      (node (ref "D63") (pin "1") (pinfunction "A_1") (pintype "passive"))
      (node (ref "R63") (pin "2") (pinfunction "2_2") (pintype "passive"))
      (node (ref "U8") (pin "10") (pinfunction "S7_10") (pintype "passive"))
    )
    (net (code "75") (name "/CH8-8") (class "Default")
      (node (ref "D64") (pin "1") (pinfunction "A_1") (pintype "passive"))
      (node (ref "R64") (pin "2") (pinfunction "2_2") (pintype "passive"))
      (node (ref "U8") (pin "9") (pinfunction "S8_9") (pintype "passive"))
    )
    (net (code "76") (name "/CH9") (class "Default")
      (node (ref "P1") (pin "18") (pinfunction "18_18") (pintype "passive"))
      (node (ref "U9") (pin "8") (pinfunction "D_8") (pintype "passive"))
    )
    (net (code "77") (name "/CH9-1") (class "Default")
      (node (ref "D65") (pin "1") (pinfunction "A_1") (pintype "passive"))
      (node (ref "R65") (pin "2") (pinfunction "2_2") (pintype "passive"))
      (node (ref "U9") (pin "4") (pinfunction "S1_4") (pintype "passive"))
    )
    (net (code "78") (name "/CH9-2") (class "Default")
      (node (ref "D66") (pin "1") (pinfunction "A_1") (pintype "passive"))
      (node (ref "R66") (pin "2") (pinfunction "2_2") (pintype "passive"))
      (node (ref "U9") (pin "5") (pinfunction "S2_5") (pintype "passive"))
    )
    (net (code "79") (name "/CH9-3") (class "Default")
      (node (ref "D67") (pin "1") (pinfunction "A_1") (pintype "passive"))
      (node (ref "R67") (pin "2") (pinfunction "2_2") (pintype "passive"))
      (node (ref "U9") (pin "6") (pinfunction "S3_6") (pintype "passive"))
    )
    (net (code "80") (name "/CH9-4") (class "Default")
      (node (ref "D68") (pin "1") (pinfunction "A_1") (pintype "passive"))
      (node (ref "R68") (pin "2") (pinfunction "2_2") (pintype "passive"))
      (node (ref "U9") (pin "7") (pinfunction "S4_7") (pintype "passive"))
    )
    (net (code "81") (name "/CH9-5") (class "Default")
      (node (ref "D69") (pin "1") (pinfunction "A_1") (pintype "passive"))
      (node (ref "R69") (pin "2") (pinfunction "2_2") (pintype "passive"))
      (node (ref "U9") (pin "12") (pinfunction "S5_12") (pintype "passive"))
    )
    (net (code "82") (name "/CH9-6") (class "Default")
      (node (ref "D70") (pin "1") (pinfunction "A_1") (pintype "passive"))
      (node (ref "R70") (pin "2") (pinfunction "2_2") (pintype "passive"))
      (node (ref "U9") (pin "11") (pinfunction "S6_11") (pintype "passive"))
    )
    (net (code "83") (name "/CH9-7") (class "Default")
      (node (ref "D71") (pin "1") (pinfunction "A_1") (pintype "passive"))
      (node (ref "R71") (pin "2") (pinfunction "2_2") (pintype "passive"))
      (node (ref "U9") (pin "10") (pinfunction "S7_10") (pintype "passive"))
    )
    (net (code "84") (name "/CH9-8") (class "Default")
      (node (ref "D72") (pin "1") (pinfunction "A_1") (pintype "passive"))
      (node (ref "R72") (pin "2") (pinfunction "2_2") (pintype "passive"))
      (node (ref "U9") (pin "9") (pinfunction "S8_9") (pintype "passive"))
    )
    (net (code "85") (name "/CH10") (class "Default")
      (node (ref "P1") (pin "20") (pinfunction "20_20") (pintype "passive"))
      (node (ref "U10") (pin "8") (pinfunction "D_8") (pintype "passive"))
    )
    (net (code "86") (name "/CH10-1") (class "Default")
      (node (ref "D73") (pin "1") (pinfunction "A_1") (pintype "passive"))
      (node (ref "R73") (pin "2") (pinfunction "2_2") (pintype "passive"))
      (node (ref "U10") (pin "4") (pinfunction "S1_4") (pintype "passive"))
    )
    (net (code "87") (name "/CH10-2") (class "Default")
      (node (ref "D74") (pin "1") (pinfunction "A_1") (pintype "passive"))
      (node (ref "R74") (pin "2") (pinfunction "2_2") (pintype "passive"))
      (node (ref "U10") (pin "5") (pinfunction "S2_5") (pintype "passive"))
    )
    (net (code "88") (name "/CH10-3") (class "Default")
      (node (ref "D75") (pin "1") (pinfunction "A_1") (pintype "passive"))
      (node (ref "R75") (pin "2") (pinfunction "2_2") (pintype "passive"))
      (node (ref "U10") (pin "6") (pinfunction "S3_6") (pintype "passive"))
    )
    (net (code "89") (name "/CH10-4") (class "Default")
      (node (ref "D76") (pin "1") (pinfunction "A_1") (pintype "passive"))
      (node (ref "R76") (pin "2") (pinfunction "2_2") (pintype "passive"))
      (node (ref "U10") (pin "7") (pinfunction "S4_7") (pintype "passive"))
    )
    (net (code "90") (name "/CH10-5") (class "Default")
      (node (ref "D77") (pin "1") (pinfunction "A_1") (pintype "passive"))
      (node (ref "R77") (pin "2") (pinfunction "2_2") (pintype "passive"))
      (node (ref "U10") (pin "12") (pinfunction "S5_12") (pintype "passive"))
    )
    (net (code "91") (name "/CH10-6") (class "Default")
      (node (ref "D78") (pin "1") (pinfunction "A_1") (pintype "passive"))
      (node (ref "R78") (pin "2") (pinfunction "2_2") (pintype "passive"))
      (node (ref "U10") (pin "11") (pinfunction "S6_11") (pintype "passive"))
    )
    (net (code "92") (name "/CH10-7") (class "Default")
      (node (ref "D79") (pin "1") (pinfunction "A_1") (pintype "passive"))
      (node (ref "R79") (pin "2") (pinfunction "2_2") (pintype "passive"))
      (node (ref "U10") (pin "10") (pinfunction "S7_10") (pintype "passive"))
    )
    (net (code "93") (name "/CH10-8") (class "Default")
      (node (ref "D80") (pin "1") (pinfunction "A_1") (pintype "passive"))
      (node (ref "R80") (pin "2") (pinfunction "2_2") (pintype "passive"))
      (node (ref "U10") (pin "9") (pinfunction "S8_9") (pintype "passive"))
    )
    (net (code "94") (name "/CH11") (class "Default")
      (node (ref "P1") (pin "22") (pinfunction "22_22") (pintype "passive"))
      (node (ref "U11") (pin "8") (pinfunction "D_8") (pintype "passive"))
    )
    (net (code "95") (name "/CH11-1") (class "Default")
      (node (ref "D81") (pin "1") (pinfunction "A_1") (pintype "passive"))
      (node (ref "R81") (pin "2") (pinfunction "2_2") (pintype "passive"))
      (node (ref "U11") (pin "4") (pinfunction "S1_4") (pintype "passive"))
    )
    (net (code "96") (name "/CH11-2") (class "Default")
      (node (ref "D82") (pin "1") (pinfunction "A_1") (pintype "passive"))
      (node (ref "R82") (pin "2") (pinfunction "2_2") (pintype "passive"))
      (node (ref "U11") (pin "5") (pinfunction "S2_5") (pintype "passive"))
    )
    (net (code "97") (name "/CH11-3") (class "Default")
      (node (ref "D83") (pin "1") (pinfunction "A_1") (pintype "passive"))
      (node (ref "R83") (pin "2") (pinfunction "2_2") (pintype "passive"))
      (node (ref "U11") (pin "6") (pinfunction "S3_6") (pintype "passive"))
    )
    (net (code "98") (name "/CH11-4") (class "Default")
      (node (ref "D84") (pin "1") (pinfunction "A_1") (pintype "passive"))
      (node (ref "R84") (pin "2") (pinfunction "2_2") (pintype "passive"))
      (node (ref "U11") (pin "7") (pinfunction "S4_7") (pintype "passive"))
    )
    (net (code "99") (name "/CH11-5") (class "Default")
      (node (ref "D85") (pin "1") (pinfunction "A_1") (pintype "passive"))
      (node (ref "R85") (pin "2") (pinfunction "2_2") (pintype "passive"))
      (node (ref "U11") (pin "12") (pinfunction "S5_12") (pintype "passive"))
    )
    (net (code "100") (name "/CH11-6") (class "Default")
      (node (ref "D86") (pin "1") (pinfunction "A_1") (pintype "passive"))
      (node (ref "R86") (pin "2") (pinfunction "2_2") (pintype "passive"))
      (node (ref "U11") (pin "11") (pinfunction "S6_11") (pintype "passive"))
    )
    (net (code "101") (name "/CH11-7") (class "Default")
      (node (ref "D87") (pin "1") (pinfunction "A_1") (pintype "passive"))
      (node (ref "R87") (pin "2") (pinfunction "2_2") (pintype "passive"))
      (node (ref "U11") (pin "10") (pinfunction "S7_10") (pintype "passive"))
    )
    (net (code "102") (name "/CH11-8") (class "Default")
      (node (ref "D88") (pin "1") (pinfunction "A_1") (pintype "passive"))
      (node (ref "R88") (pin "2") (pinfunction "2_2") (pintype "passive"))
      (node (ref "U11") (pin "9") (pinfunction "S8_9") (pintype "passive"))
    )
    (net (code "103") (name "/CH12") (class "Default")
      (node (ref "P1") (pin "24") (pinfunction "24_24") (pintype "passive"))
      (node (ref "U12") (pin "8") (pinfunction "D_8") (pintype "passive"))
    )
    (net (code "104") (name "/CH12-1") (class "Default")
      (node (ref "D89") (pin "1") (pinfunction "A_1") (pintype "passive"))
      (node (ref "R89") (pin "2") (pinfunction "2_2") (pintype "passive"))
      (node (ref "U12") (pin "4") (pinfunction "S1_4") (pintype "passive"))
    )
    (net (code "105") (name "/CH12-2") (class "Default")
      (node (ref "D90") (pin "1") (pinfunction "A_1") (pintype "passive"))
      (node (ref "R90") (pin "2") (pinfunction "2_2") (pintype "passive"))
      (node (ref "U12") (pin "5") (pinfunction "S2_5") (pintype "passive"))
    )
    (net (code "106") (name "/CH12-3") (class "Default")
      (node (ref "D91") (pin "1") (pinfunction "A_1") (pintype "passive"))
      (node (ref "R91") (pin "2") (pinfunction "2_2") (pintype "passive"))
      (node (ref "U12") (pin "6") (pinfunction "S3_6") (pintype "passive"))
    )
    (net (code "107") (name "/CH12-4") (class "Default")
      (node (ref "D92") (pin "1") (pinfunction "A_1") (pintype "passive"))
      (node (ref "R92") (pin "2") (pinfunction "2_2") (pintype "passive"))
      (node (ref "U12") (pin "7") (pinfunction "S4_7") (pintype "passive"))
    )
    (net (code "108") (name "/CH12-5") (class "Default")
      (node (ref "D93") (pin "1") (pinfunction "A_1") (pintype "passive"))
      (node (ref "R93") (pin "2") (pinfunction "2_2") (pintype "passive"))
      (node (ref "U12") (pin "12") (pinfunction "S5_12") (pintype "passive"))
    )
    (net (code "109") (name "/CH12-6") (class "Default")
      (node (ref "D94") (pin "1") (pinfunction "A_1") (pintype "passive"))
      (node (ref "R94") (pin "2") (pinfunction "2_2") (pintype "passive"))
      (node (ref "U12") (pin "11") (pinfunction "S6_11") (pintype "passive"))
    )
    (net (code "110") (name "/CH12-7") (class "Default")
      (node (ref "D95") (pin "1") (pinfunction "A_1") (pintype "passive"))
      (node (ref "R95") (pin "2") (pinfunction "2_2") (pintype "passive"))
      (node (ref "U12") (pin "10") (pinfunction "S7_10") (pintype "passive"))
    )
    (net (code "111") (name "/CH12-8") (class "Default")
      (node (ref "D96") (pin "1") (pinfunction "A_1") (pintype "passive"))
      (node (ref "R96") (pin "2") (pinfunction "2_2") (pintype "passive"))
      (node (ref "U12") (pin "9") (pinfunction "S8_9") (pintype "passive"))
    )
    (net (code "112") (name "/EN") (class "Default")
      (node (ref "P1") (pin "7") (pinfunction "7_7") (pintype "passive"))
      (node (ref "U1") (pin "2") (pinfunction "EN_2") (pintype "passive"))
      (node (ref "U10") (pin "2") (pinfunction "EN_2") (pintype "passive"))
      (node (ref "U11") (pin "2") (pinfunction "EN_2") (pintype "passive"))
      (node (ref "U12") (pin "2") (pinfunction "EN_2") (pintype "passive"))
      (node (ref "U2") (pin "2") (pinfunction "EN_2") (pintype "passive"))
      (node (ref "U3") (pin "2") (pinfunction "EN_2") (pintype "passive"))
      (node (ref "U4") (pin "2") (pinfunction "EN_2") (pintype "passive"))
      (node (ref "U5") (pin "2") (pinfunction "EN_2") (pintype "passive"))
      (node (ref "U6") (pin "2") (pinfunction "EN_2") (pintype "passive"))
      (node (ref "U7") (pin "2") (pinfunction "EN_2") (pintype "passive"))
      (node (ref "U8") (pin "2") (pinfunction "EN_2") (pintype "passive"))
      (node (ref "U9") (pin "2") (pinfunction "EN_2") (pintype "passive"))
    )
    (net (code "113") (name "GND") (class "Default")
      (node (ref "C1") (pin "1") (pinfunction "1_1") (pintype "passive"))
      (node (ref "C2") (pin "1") (pinfunction "1_1") (pintype "passive"))
      (node (ref "C3") (pin "1") (pinfunction "1_1") (pintype "passive"))
      (node (ref "C4") (pin "1") (pinfunction "1_1") (pintype "passive"))
      (node (ref "P1") (pin "17") (pinfunction "17_17") (pintype "passive"))
      (node (ref "P1") (pin "19") (pinfunction "19_19") (pintype "passive"))
      (node (ref "R1") (pin "1") (pinfunction "1_1") (pintype "passive"))
      (node (ref "R10") (pin "1") (pinfunction "1_1") (pintype "passive"))
      (node (ref "R11") (pin "1") (pinfunction "1_1") (pintype "passive"))
      (node (ref "R12") (pin "1") (pinfunction "1_1") (pintype "passive"))
      (node (ref "R13") (pin "1") (pinfunction "1_1") (pintype "passive"))
      (node (ref "R14") (pin "1") (pinfunction "1_1") (pintype "passive"))
      (node (ref "R15") (pin "1") (pinfunction "1_1") (pintype "passive"))
      (node (ref "R16") (pin "1") (pinfunction "1_1") (pintype "passive"))
      (node (ref "R17") (pin "1") (pinfunction "1_1") (pintype "passive"))
      (node (ref "R18") (pin "1") (pinfunction "1_1") (pintype "passive"))
      (node (ref "R19") (pin "1") (pinfunction "1_1") (pintype "passive"))
      (node (ref "R2") (pin "1") (pinfunction "1_1") (pintype "passive"))
      (node (ref "R20") (pin "1") (pinfunction "1_1") (pintype "passive"))
      (node (ref "R21") (pin "1") (pinfunction "1_1") (pintype "passive"))
      (node (ref "R22") (pin "1") (pinfunction "1_1") (pintype "passive"))
      (node (ref "R23") (pin "1") (pinfunction "1_1") (pintype "passive"))
      (node (ref "R24") (pin "1") (pinfunction "1_1") (pintype "passive"))
      (node (ref "R25") (pin "1") (pinfunction "1_1") (pintype "passive"))
      (node (ref "R26") (pin "1") (pinfunction "1_1") (pintype "passive"))
      (node (ref "R27") (pin "1") (pinfunction "1_1") (pintype "passive"))
      (node (ref "R28") (pin "1") (pinfunction "1_1") (pintype "passive"))
      (node (ref "R29") (pin "1") (pinfunction "1_1") (pintype "passive"))
      (node (ref "R3") (pin "1") (pinfunction "1_1") (pintype "passive"))
      (node (ref "R30") (pin "1") (pinfunction "1_1") (pintype "passive"))
      (node (ref "R31") (pin "1") (pinfunction "1_1") (pintype "passive"))
      (node (ref "R32") (pin "1") (pinfunction "1_1") (pintype "passive"))
      (node (ref "R33") (pin "1") (pinfunction "1_1") (pintype "passive"))
      (node (ref "R34") (pin "1") (pinfunction "1_1") (pintype "passive"))
      (node (ref "R35") (pin "1") (pinfunction "1_1") (pintype "passive"))
      (node (ref "R36") (pin "1") (pinfunction "1_1") (pintype "passive"))
      (node (ref "R37") (pin "1") (pinfunction "1_1") (pintype "passive"))
      (node (ref "R38") (pin "1") (pinfunction "1_1") (pintype "passive"))
      (node (ref "R39") (pin "1") (pinfunction "1_1") (pintype "passive"))
      (node (ref "R4") (pin "1") (pinfunction "1_1") (pintype "passive"))
      (node (ref "R40") (pin "1") (pinfunction "1_1") (pintype "passive"))
      (node (ref "R41") (pin "1") (pinfunction "1_1") (pintype "passive"))
      (node (ref "R42") (pin "1") (pinfunction "1_1") (pintype "passive"))
      (node (ref "R43") (pin "1") (pinfunction "1_1") (pintype "passive"))
      (node (ref "R44") (pin "1") (pinfunction "1_1") (pintype "passive"))
      (node (ref "R45") (pin "1") (pinfunction "1_1") (pintype "passive"))
      (node (ref "R46") (pin "1") (pinfunction "1_1") (pintype "passive"))
      (node (ref "R47") (pin "1") (pinfunction "1_1") (pintype "passive"))
      (node (ref "R48") (pin "1") (pinfunction "1_1") (pintype "passive"))
      (node (ref "R49") (pin "1") (pinfunction "1_1") (pintype "passive"))
      (node (ref "R5") (pin "1") (pinfunction "1_1") (pintype "passive"))
      (node (ref "R50") (pin "1") (pinfunction "1_1") (pintype "passive"))
      (node (ref "R51") (pin "1") (pinfunction "1_1") (pintype "passive"))
      (node (ref "R52") (pin "1") (pinfunction "1_1") (pintype "passive"))
      (node (ref "R53") (pin "1") (pinfunction "1_1") (pintype "passive"))
      (node (ref "R54") (pin "1") (pinfunction "1_1") (pintype "passive"))
      (node (ref "R55") (pin "1") (pinfunction "1_1") (pintype "passive"))
      (node (ref "R56") (pin "1") (pinfunction "1_1") (pintype "passive"))
      (node (ref "R57") (pin "1") (pinfunction "1_1") (pintype "passive"))
      (node (ref "R58") (pin "1") (pinfunction "1_1") (pintype "passive"))
      (node (ref "R59") (pin "1") (pinfunction "1_1") (pintype "passive"))
      (node (ref "R6") (pin "1") (pinfunction "1_1") (pintype "passive"))
      (node (ref "R60") (pin "1") (pinfunction "1_1") (pintype "passive"))
      (node (ref "R61") (pin "1") (pinfunction "1_1") (pintype "passive"))
      (node (ref "R62") (pin "1") (pinfunction "1_1") (pintype "passive"))
      (node (ref "R63") (pin "1") (pinfunction "1_1") (pintype "passive"))
      (node (ref "R64") (pin "1") (pinfunction "1_1") (pintype "passive"))
      (node (ref "R65") (pin "1") (pinfunction "1_1") (pintype "passive"))
      (node (ref "R66") (pin "1") (pinfunction "1_1") (pintype "passive"))
      (node (ref "R67") (pin "1") (pinfunction "1_1") (pintype "passive"))
      (node (ref "R68") (pin "1") (pinfunction "1_1") (pintype "passive"))
      (node (ref "R69") (pin "1") (pinfunction "1_1") (pintype "passive"))
      (node (ref "R7") (pin "1") (pinfunction "1_1") (pintype "passive"))
      (node (ref "R70") (pin "1") (pinfunction "1_1") (pintype "passive"))
      (node (ref "R71") (pin "1") (pinfunction "1_1") (pintype "passive"))
      (node (ref "R72") (pin "1") (pinfunction "1_1") (pintype "passive"))
      (node (ref "R73") (pin "1") (pinfunction "1_1") (pintype "passive"))
      (node (ref "R74") (pin "1") (pinfunction "1_1") (pintype "passive"))
      (node (ref "R75") (pin "1") (pinfunction "1_1") (pintype "passive"))
      (node (ref "R76") (pin "1") (pinfunction "1_1") (pintype "passive"))
      (node (ref "R77") (pin "1") (pinfunction "1_1") (pintype "passive"))
      (node (ref "R78") (pin "1") (pinfunction "1_1") (pintype "passive"))
      (node (ref "R79") (pin "1") (pinfunction "1_1") (pintype "passive"))
      (node (ref "R8") (pin "1") (pinfunction "1_1") (pintype "passive"))
      (node (ref "R80") (pin "1") (pinfunction "1_1") (pintype "passive"))
      (node (ref "R81") (pin "1") (pinfunction "1_1") (pintype "passive"))
      (node (ref "R82") (pin "1") (pinfunction "1_1") (pintype "passive"))
      (node (ref "R83") (pin "1") (pinfunction "1_1") (pintype "passive"))
      (node (ref "R84") (pin "1") (pinfunction "1_1") (pintype "passive"))
      (node (ref "R85") (pin "1") (pinfunction "1_1") (pintype "passive"))
      (node (ref "R86") (pin "1") (pinfunction "1_1") (pintype "passive"))
      (node (ref "R87") (pin "1") (pinfunction "1_1") (pintype "passive"))
      (node (ref "R88") (pin "1") (pinfunction "1_1") (pintype "passive"))
      (node (ref "R89") (pin "1") (pinfunction "1_1") (pintype "passive"))
      (node (ref "R9") (pin "1") (pinfunction "1_1") (pintype "passive"))
      (node (ref "R90") (pin "1") (pinfunction "1_1") (pintype "passive"))
      (node (ref "R91") (pin "1") (pinfunction "1_1") (pintype "passive"))
      (node (ref "R92") (pin "1") (pinfunction "1_1") (pintype "passive"))
      (node (ref "R93") (pin "1") (pinfunction "1_1") (pintype "passive"))
      (node (ref "R94") (pin "1") (pinfunction "1_1") (pintype "passive"))
      (node (ref "R95") (pin "1") (pinfunction "1_1") (pintype "passive"))
      (node (ref "R96") (pin "1") (pinfunction "1_1") (pintype "passive"))
      (node (ref "U1") (pin "14") (pinfunction "GND_14") (pintype "passive"))
      (node (ref "U1") (pin "3") (pinfunction "VSS_3") (pintype "passive"))
      (node (ref "U10") (pin "14") (pinfunction "GND_14") (pintype "passive"))
      (node (ref "U10") (pin "3") (pinfunction "VSS_3") (pintype "passive"))
      (node (ref "U11") (pin "14") (pinfunction "GND_14") (pintype "passive"))
      (node (ref "U11") (pin "3") (pinfunction "VSS_3") (pintype "passive"))
      (node (ref "U12") (pin "14") (pinfunction "GND_14") (pintype "passive"))
      (node (ref "U12") (pin "3") (pinfunction "VSS_3") (pintype "passive"))
      (node (ref "U2") (pin "14") (pinfunction "GND_14") (pintype "passive"))
      (node (ref "U2") (pin "3") (pinfunction "VSS_3") (pintype "passive"))
      (node (ref "U3") (pin "14") (pinfunction "GND_14") (pintype "passive"))
      (node (ref "U3") (pin "3") (pinfunction "VSS_3") (pintype "passive"))
      (node (ref "U4") (pin "14") (pinfunction "GND_14") (pintype "passive"))
      (node (ref "U4") (pin "3") (pinfunction "VSS_3") (pintype "passive"))
      (node (ref "U5") (pin "14") (pinfunction "GND_14") (pintype "passive"))
      (node (ref "U5") (pin "3") (pinfunction "VSS_3") (pintype "passive"))
      (node (ref "U6") (pin "14") (pinfunction "GND_14") (pintype "passive"))
      (node (ref "U6") (pin "3") (pinfunction "VSS_3") (pintype "passive"))
      (node (ref "U7") (pin "14") (pinfunction "GND_14") (pintype "passive"))
      (node (ref "U7") (pin "3") (pinfunction "VSS_3") (pintype "passive"))
      (node (ref "U8") (pin "14") (pinfunction "GND_14") (pintype "passive"))
      (node (ref "U8") (pin "3") (pinfunction "VSS_3") (pintype "passive"))
      (node (ref "U9") (pin "14") (pinfunction "GND_14") (pintype "passive"))
      (node (ref "U9") (pin "3") (pinfunction "VSS_3") (pintype "passive"))
    )
    (net (code "114") (name "VCC3.3") (class "Default")
      (node (ref "C3") (pin "2") (pinfunction "2_2") (pintype "passive"))
      (node (ref "C4") (pin "2") (pinfunction "2_2") (pintype "passive"))
      (node (ref "D1") (pin "2") (pinfunction "K_2") (pintype "passive"))
      (node (ref "D10") (pin "2") (pinfunction "K_2") (pintype "passive"))
      (node (ref "D11") (pin "2") (pinfunction "K_2") (pintype "passive"))
      (node (ref "D12") (pin "2") (pinfunction "K_2") (pintype "passive"))
      (node (ref "D13") (pin "2") (pinfunction "K_2") (pintype "passive"))
      (node (ref "D14") (pin "2") (pinfunction "K_2") (pintype "passive"))
      (node (ref "D15") (pin "2") (pinfunction "K_2") (pintype "passive"))
      (node (ref "D16") (pin "2") (pinfunction "K_2") (pintype "passive"))
      (node (ref "D17") (pin "2") (pinfunction "K_2") (pintype "passive"))
      (node (ref "D18") (pin "2") (pinfunction "K_2") (pintype "passive"))
      (node (ref "D19") (pin "2") (pinfunction "K_2") (pintype "passive"))
      (node (ref "D2") (pin "2") (pinfunction "K_2") (pintype "passive"))
      (node (ref "D20") (pin "2") (pinfunction "K_2") (pintype "passive"))
      (node (ref "D21") (pin "2") (pinfunction "K_2") (pintype "passive"))
      (node (ref "D22") (pin "2") (pinfunction "K_2") (pintype "passive"))
      (node (ref "D23") (pin "2") (pinfunction "K_2") (pintype "passive"))
      (node (ref "D24") (pin "2") (pinfunction "K_2") (pintype "passive"))
      (node (ref "D25") (pin "2") (pinfunction "K_2") (pintype "passive"))
      (node (ref "D26") (pin "2") (pinfunction "K_2") (pintype "passive"))
      (node (ref "D27") (pin "2") (pinfunction "K_2") (pintype "passive"))
      (node (ref "D28") (pin "2") (pinfunction "K_2") (pintype "passive"))
      (node (ref "D29") (pin "2") (pinfunction "K_2") (pintype "passive"))
      (node (ref "D3") (pin "2") (pinfunction "K_2") (pintype "passive"))
      (node (ref "D30") (pin "2") (pinfunction "K_2") (pintype "passive"))
      (node (ref "D31") (pin "2") (pinfunction "K_2") (pintype "passive"))
      (node (ref "D32") (pin "2") (pinfunction "K_2") (pintype "passive"))
      (node (ref "D33") (pin "2") (pinfunction "K_2") (pintype "passive"))
      (node (ref "D34") (pin "2") (pinfunction "K_2") (pintype "passive"))
      (node (ref "D35") (pin "2") (pinfunction "K_2") (pintype "passive"))
      (node (ref "D36") (pin "2") (pinfunction "K_2") (pintype "passive"))
      (node (ref "D37") (pin "2") (pinfunction "K_2") (pintype "passive"))
      (node (ref "D38") (pin "2") (pinfunction "K_2") (pintype "passive"))
      (node (ref "D39") (pin "2") (pinfunction "K_2") (pintype "passive"))
      (node (ref "D4") (pin "2") (pinfunction "K_2") (pintype "passive"))
      (node (ref "D40") (pin "2") (pinfunction "K_2") (pintype "passive"))
      (node (ref "D41") (pin "2") (pinfunction "K_2") (pintype "passive"))
      (node (ref "D42") (pin "2") (pinfunction "K_2") (pintype "passive"))
      (node (ref "D43") (pin "2") (pinfunction "K_2") (pintype "passive"))
      (node (ref "D44") (pin "2") (pinfunction "K_2") (pintype "passive"))
      (node (ref "D45") (pin "2") (pinfunction "K_2") (pintype "passive"))
      (node (ref "D46") (pin "2") (pinfunction "K_2") (pintype "passive"))
      (node (ref "D47") (pin "2") (pinfunction "K_2") (pintype "passive"))
      (node (ref "D48") (pin "2") (pinfunction "K_2") (pintype "passive"))
      (node (ref "D49") (pin "2") (pinfunction "K_2") (pintype "passive"))
      (node (ref "D5") (pin "2") (pinfunction "K_2") (pintype "passive"))
      (node (ref "D50") (pin "2") (pinfunction "K_2") (pintype "passive"))
      (node (ref "D51") (pin "2") (pinfunction "K_2") (pintype "passive"))
      (node (ref "D52") (pin "2") (pinfunction "K_2") (pintype "passive"))
      (node (ref "D53") (pin "2") (pinfunction "K_2") (pintype "passive"))
      (node (ref "D54") (pin "2") (pinfunction "K_2") (pintype "passive"))
      (node (ref "D55") (pin "2") (pinfunction "K_2") (pintype "passive"))
      (node (ref "D56") (pin "2") (pinfunction "K_2") (pintype "passive"))
      (node (ref "D57") (pin "2") (pinfunction "K_2") (pintype "passive"))
      (node (ref "D58") (pin "2") (pinfunction "K_2") (pintype "passive"))
      (node (ref "D59") (pin "2") (pinfunction "K_2") (pintype "passive"))
      (node (ref "D6") (pin "2") (pinfunction "K_2") (pintype "passive"))
      (node (ref "D60") (pin "2") (pinfunction "K_2") (pintype "passive"))
      (node (ref "D61") (pin "2") (pinfunction "K_2") (pintype "passive"))
      (node (ref "D62") (pin "2") (pinfunction "K_2") (pintype "passive"))
      (node (ref "D63") (pin "2") (pinfunction "K_2") (pintype "passive"))
      (node (ref "D64") (pin "2") (pinfunction "K_2") (pintype "passive"))
      (node (ref "D65") (pin "2") (pinfunction "K_2") (pintype "passive"))
      (node (ref "D66") (pin "2") (pinfunction "K_2") (pintype "passive"))
      (node (ref "D67") (pin "2") (pinfunction "K_2") (pintype "passive"))
      (node (ref "D68") (pin "2") (pinfunction "K_2") (pintype "passive"))
      (node (ref "D69") (pin "2") (pinfunction "K_2") (pintype "passive"))
      (node (ref "D7") (pin "2") (pinfunction "K_2") (pintype "passive"))
      (node (ref "D70") (pin "2") (pinfunction "K_2") (pintype "passive"))
      (node (ref "D71") (pin "2") (pinfunction "K_2") (pintype "passive"))
      (node (ref "D72") (pin "2") (pinfunction "K_2") (pintype "passive"))
      (node (ref "D73") (pin "2") (pinfunction "K_2") (pintype "passive"))
      (node (ref "D74") (pin "2") (pinfunction "K_2") (pintype "passive"))
      (node (ref "D75") (pin "2") (pinfunction "K_2") (pintype "passive"))
      (node (ref "D76") (pin "2") (pinfunction "K_2") (pintype "passive"))
      (node (ref "D77") (pin "2") (pinfunction "K_2") (pintype "passive"))
      (node (ref "D78") (pin "2") (pinfunction "K_2") (pintype "passive"))
      (node (ref "D79") (pin "2") (pinfunction "K_2") (pintype "passive"))
      (node (ref "D8") (pin "2") (pinfunction "K_2") (pintype "passive"))
      (node (ref "D80") (pin "2") (pinfunction "K_2") (pintype "passive"))
      (node (ref "D81") (pin "2") (pinfunction "K_2") (pintype "passive"))
      (node (ref "D82") (pin "2") (pinfunction "K_2") (pintype "passive"))
      (node (ref "D83") (pin "2") (pinfunction "K_2") (pintype "passive"))
      (node (ref "D84") (pin "2") (pinfunction "K_2") (pintype "passive"))
      (node (ref "D85") (pin "2") (pinfunction "K_2") (pintype "passive"))
      (node (ref "D86") (pin "2") (pinfunction "K_2") (pintype "passive"))
      (node (ref "D87") (pin "2") (pinfunction "K_2") (pintype "passive"))
      (node (ref "D88") (pin "2") (pinfunction "K_2") (pintype "passive"))
      (node (ref "D89") (pin "2") (pinfunction "K_2") (pintype "passive"))
      (node (ref "D9") (pin "2") (pinfunction "K_2") (pintype "passive"))
      (node (ref "D90") (pin "2") (pinfunction "K_2") (pintype "passive"))
      (node (ref "D91") (pin "2") (pinfunction "K_2") (pintype "passive"))
      (node (ref "D92") (pin "2") (pinfunction "K_2") (pintype "passive"))
      (node (ref "D93") (pin "2") (pinfunction "K_2") (pintype "passive"))
      (node (ref "D94") (pin "2") (pinfunction "K_2") (pintype "passive"))
      (node (ref "D95") (pin "2") (pinfunction "K_2") (pintype "passive"))
      (node (ref "D96") (pin "2") (pinfunction "K_2") (pintype "passive"))
      (node (ref "P1") (pin "21") (pinfunction "21_21") (pintype "passive"))
      (node (ref "P1") (pin "23") (pinfunction "23_23") (pintype "passive"))
    )
    (net (code "115") (name "VCC5V") (class "Default")
      (node (ref "C1") (pin "2") (pinfunction "2_2") (pintype "passive"))
      (node (ref "C2") (pin "2") (pinfunction "2_2") (pintype "passive"))
      (node (ref "P1") (pin "13") (pinfunction "13_13") (pintype "passive"))
      (node (ref "P1") (pin "15") (pinfunction "15_15") (pintype "passive"))
      (node (ref "U1") (pin "13") (pinfunction "VDD_13") (pintype "passive"))
      (node (ref "U10") (pin "13") (pinfunction "VDD_13") (pintype "passive"))
      (node (ref "U11") (pin "13") (pinfunction "VDD_13") (pintype "passive"))
      (node (ref "U12") (pin "13") (pinfunction "VDD_13") (pintype "passive"))
      (node (ref "U2") (pin "13") (pinfunction "VDD_13") (pintype "passive"))
      (node (ref "U3") (pin "13") (pinfunction "VDD_13") (pintype "passive"))
      (node (ref "U4") (pin "13") (pinfunction "VDD_13") (pintype "passive"))
      (node (ref "U5") (pin "13") (pinfunction "VDD_13") (pintype "passive"))
      (node (ref "U6") (pin "13") (pinfunction "VDD_13") (pintype "passive"))
      (node (ref "U7") (pin "13") (pinfunction "VDD_13") (pintype "passive"))
      (node (ref "U8") (pin "13") (pinfunction "VDD_13") (pintype "passive"))
      (node (ref "U9") (pin "13") (pinfunction "VDD_13") (pintype "passive"))
    )
    (net (code "116") (name "unconnected-(P1-Pad9)") (class "Default")
      (node (ref "P1") (pin "9") (pinfunction "9_9") (pintype "passive"))
    )
    (net (code "117") (name "unconnected-(P1-Pad11)") (class "Default")
      (node (ref "P1") (pin "11") (pinfunction "11_11") (pintype "passive"))
    )
  )
)
